# motherboard.net
KiCad netlist of a schematic drawn in EAGLE
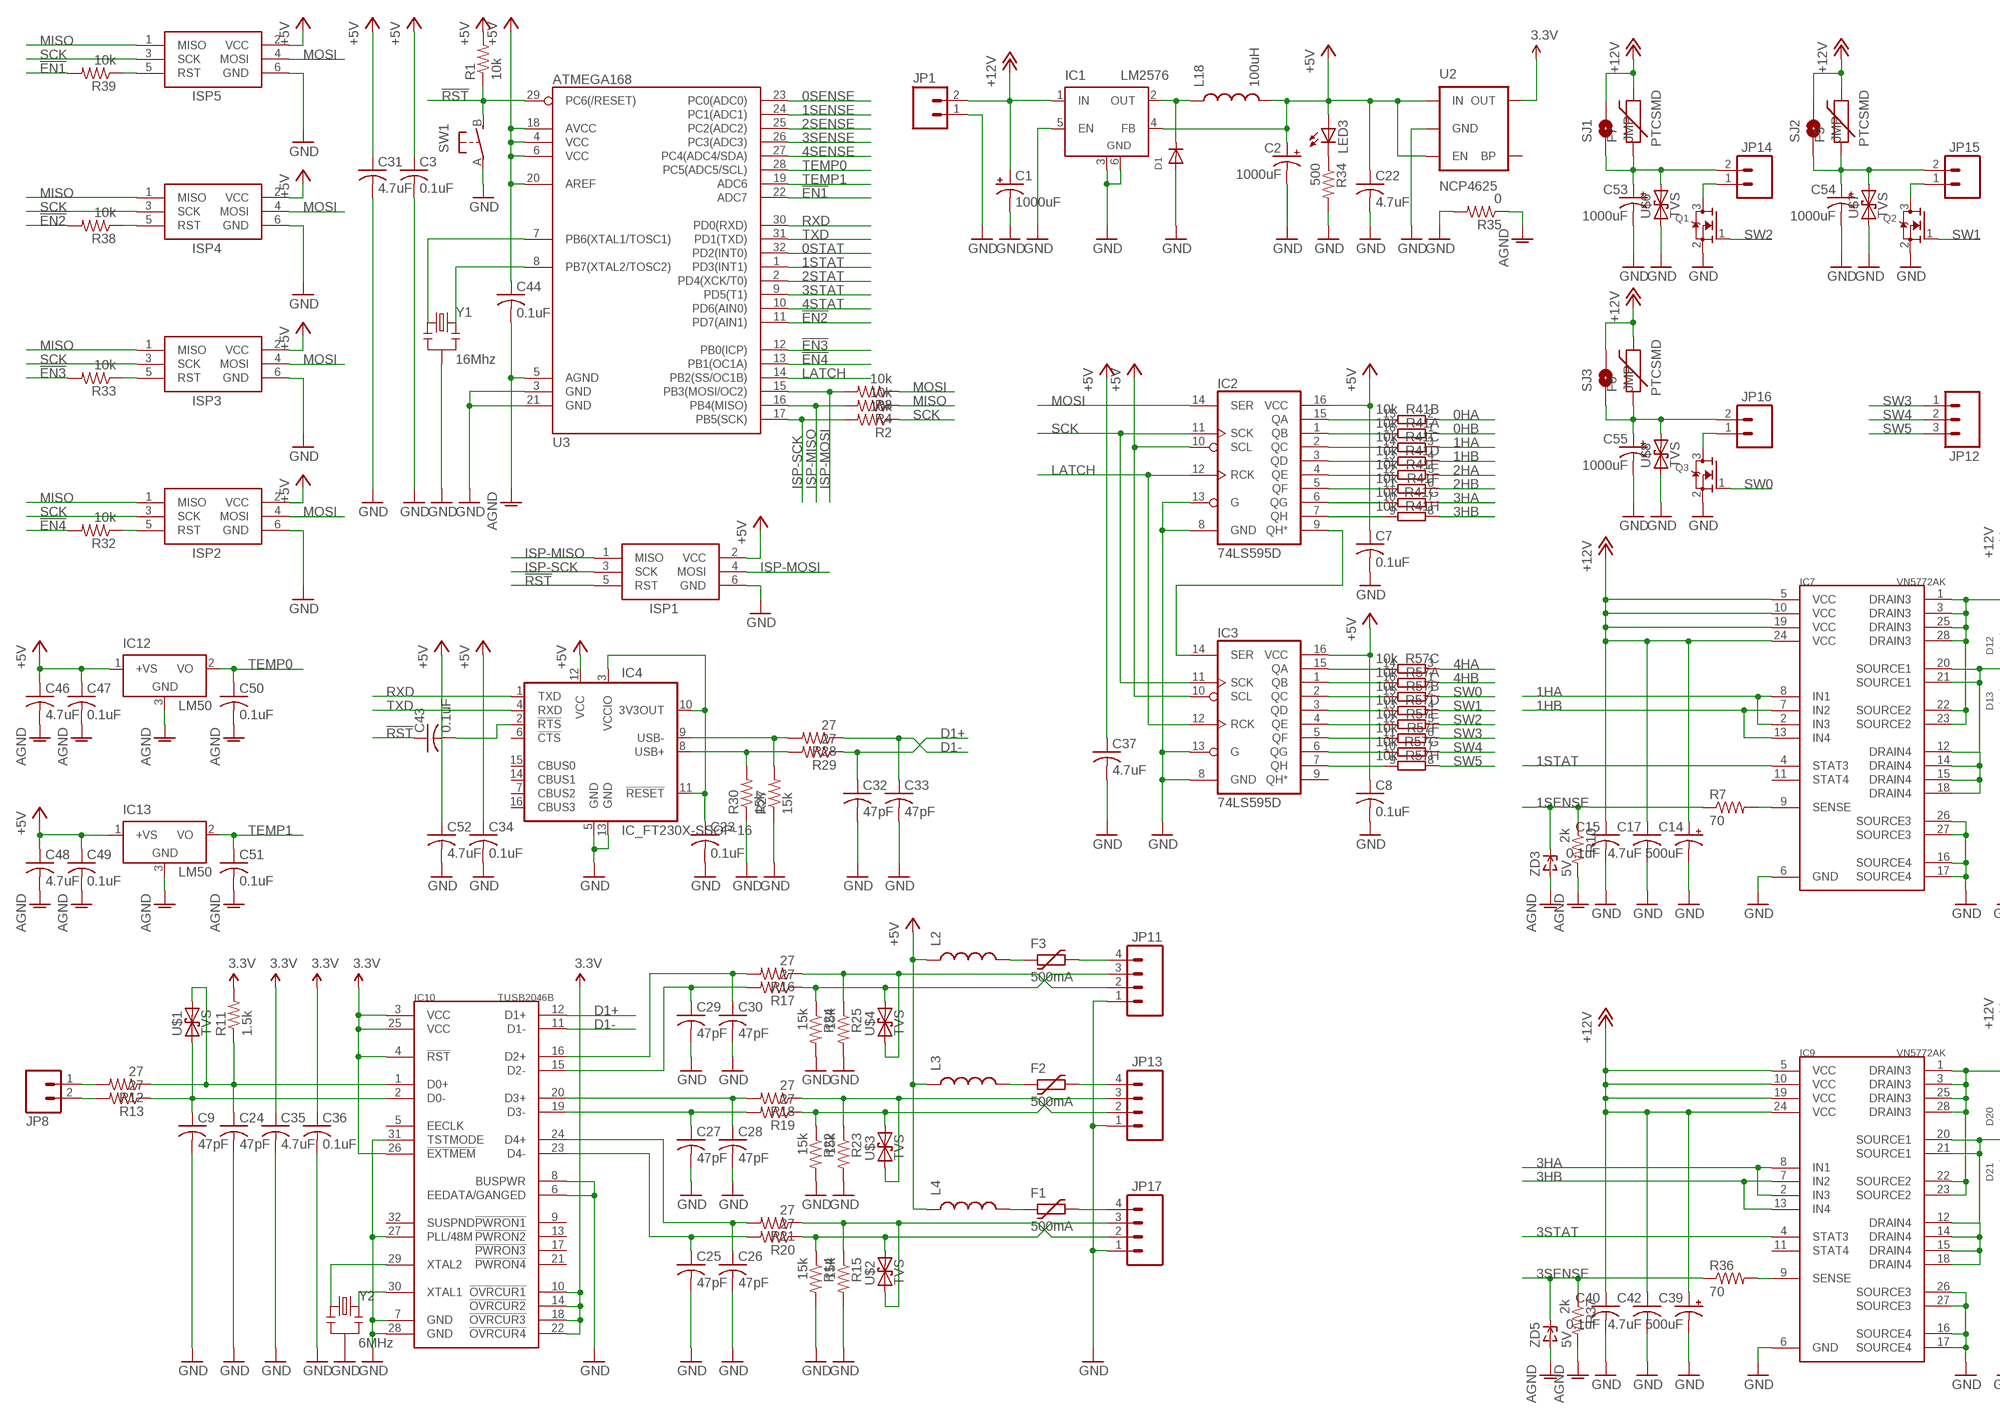
[diagram p0: schematic, sheet 1, part 1 of 2]
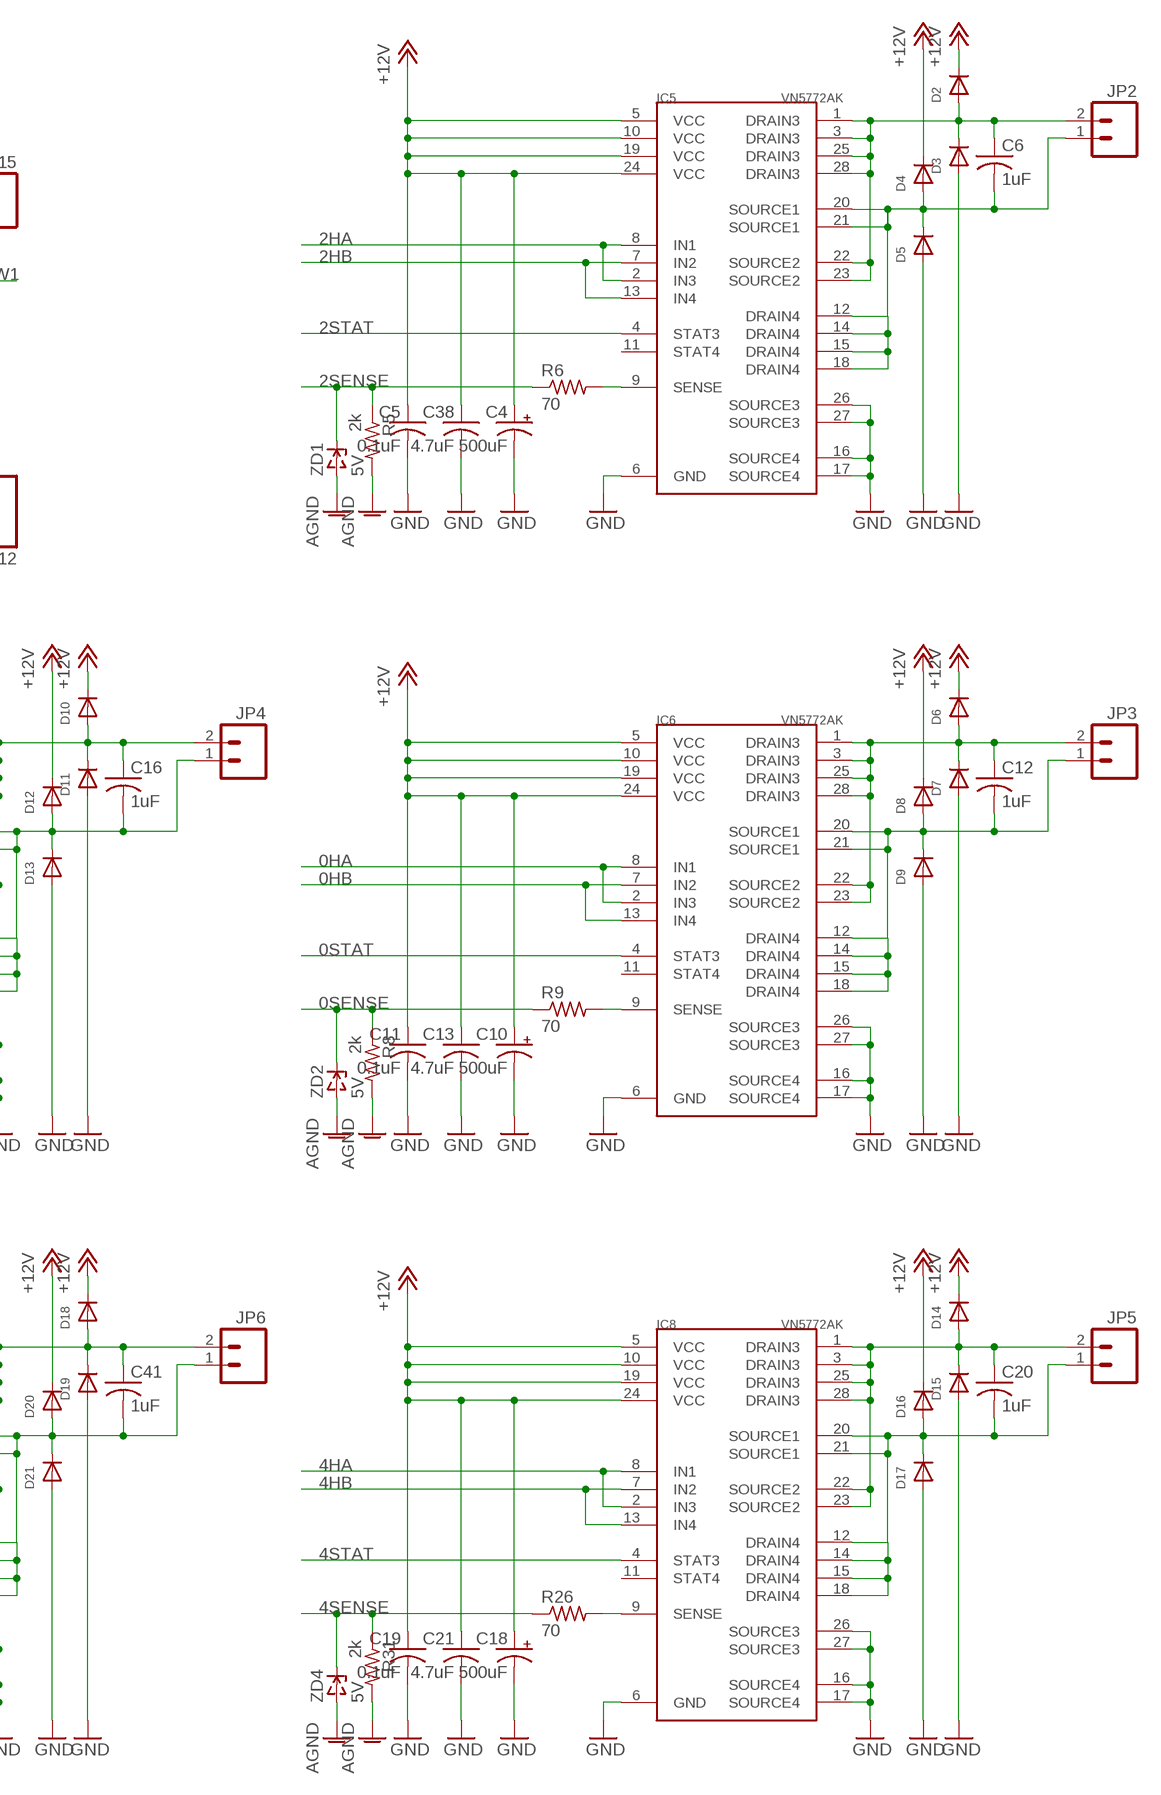
[diagram p1: schematic, sheet 1, part 2 of 2]

(export (version "E")
  (design (tool "Eeschema 10.0.6"))
  (components
    (comp (ref "C1")
      (value "1000uF")
      (footprint "eagle-import:153CLV-0807")
      (libsource (lib "eagle-import") (part "CPOL-US153CLV-0807"))
    )
    (comp (ref "C2")
      (value "1000uF")
      (footprint "eagle-import:153CLV-0807")
      (libsource (lib "eagle-import") (part "CPOL-US153CLV-0807"))
    )
    (comp (ref "C3")
      (value "0.1uF")
      (footprint "eagle-import:C1206")
      (libsource (lib "eagle-import") (part "C-USC1206"))
    )
    (comp (ref "C4")
      (value "500uF")
      (footprint "eagle-import:153CLV-0807")
      (libsource (lib "eagle-import") (part "CPOL-US153CLV-0807"))
    )
    (comp (ref "C5")
      (value "0.1uF")
      (footprint "eagle-import:C1206")
      (libsource (lib "eagle-import") (part "C-USC1206"))
    )
    (comp (ref "C6")
      (value "1uF")
      (footprint "eagle-import:C1206")
      (libsource (lib "eagle-import") (part "C-USC1206"))
    )
    (comp (ref "C7")
      (value "0.1uF")
      (footprint "eagle-import:C1206")
      (libsource (lib "eagle-import") (part "C-USC1206"))
    )
    (comp (ref "C8")
      (value "0.1uF")
      (footprint "eagle-import:C1206")
      (libsource (lib "eagle-import") (part "C-USC1206"))
    )
    (comp (ref "C9")
      (value "47pF")
      (footprint "eagle-import:C1206")
      (libsource (lib "eagle-import") (part "C-USC1206"))
    )
    (comp (ref "C10")
      (value "500uF")
      (footprint "eagle-import:153CLV-0807")
      (libsource (lib "eagle-import") (part "CPOL-US153CLV-0807"))
    )
    (comp (ref "C11")
      (value "0.1uF")
      (footprint "eagle-import:C1206")
      (libsource (lib "eagle-import") (part "C-USC1206"))
    )
    (comp (ref "C12")
      (value "1uF")
      (footprint "eagle-import:C1206")
      (libsource (lib "eagle-import") (part "C-USC1206"))
    )
    (comp (ref "C13")
      (value "4.7uF")
      (footprint "eagle-import:C1206")
      (libsource (lib "eagle-import") (part "C-USC1206"))
    )
    (comp (ref "C14")
      (value "500uF")
      (footprint "eagle-import:153CLV-0807")
      (libsource (lib "eagle-import") (part "CPOL-US153CLV-0807"))
    )
    (comp (ref "C15")
      (value "0.1uF")
      (footprint "eagle-import:C1206")
      (libsource (lib "eagle-import") (part "C-USC1206"))
    )
    (comp (ref "C16")
      (value "1uF")
      (footprint "eagle-import:C1206")
      (libsource (lib "eagle-import") (part "C-USC1206"))
    )
    (comp (ref "C17")
      (value "4.7uF")
      (footprint "eagle-import:C1206")
      (libsource (lib "eagle-import") (part "C-USC1206"))
    )
    (comp (ref "C18")
      (value "500uF")
      (footprint "eagle-import:153CLV-0807")
      (libsource (lib "eagle-import") (part "CPOL-US153CLV-0807"))
    )
    (comp (ref "C19")
      (value "0.1uF")
      (footprint "eagle-import:C1206")
      (libsource (lib "eagle-import") (part "C-USC1206"))
    )
    (comp (ref "C20")
      (value "1uF")
      (footprint "eagle-import:C1206")
      (libsource (lib "eagle-import") (part "C-USC1206"))
    )
    (comp (ref "C21")
      (value "4.7uF")
      (footprint "eagle-import:C1206")
      (libsource (lib "eagle-import") (part "C-USC1206"))
    )
    (comp (ref "C22")
      (value "4.7uF")
      (footprint "eagle-import:C1206")
      (libsource (lib "eagle-import") (part "C-USC1206"))
    )
    (comp (ref "C23")
      (value "0.1uF")
      (footprint "eagle-import:C1206")
      (libsource (lib "eagle-import") (part "C-USC1206"))
    )
    (comp (ref "C24")
      (value "47pF")
      (footprint "eagle-import:C1206")
      (libsource (lib "eagle-import") (part "C-USC1206"))
    )
    (comp (ref "C25")
      (value "47pF")
      (footprint "eagle-import:C1206")
      (libsource (lib "eagle-import") (part "C-USC1206"))
    )
    (comp (ref "C26")
      (value "47pF")
      (footprint "eagle-import:C1206")
      (libsource (lib "eagle-import") (part "C-USC1206"))
    )
    (comp (ref "C27")
      (value "47pF")
      (footprint "eagle-import:C1206")
      (libsource (lib "eagle-import") (part "C-USC1206"))
    )
    (comp (ref "C28")
      (value "47pF")
      (footprint "eagle-import:C1206")
      (libsource (lib "eagle-import") (part "C-USC1206"))
    )
    (comp (ref "C29")
      (value "47pF")
      (footprint "eagle-import:C1206")
      (libsource (lib "eagle-import") (part "C-USC1206"))
    )
    (comp (ref "C30")
      (value "47pF")
      (footprint "eagle-import:C1206")
      (libsource (lib "eagle-import") (part "C-USC1206"))
    )
    (comp (ref "C31")
      (value "4.7uF")
      (footprint "eagle-import:C1206")
      (libsource (lib "eagle-import") (part "C-USC1206"))
    )
    (comp (ref "C32")
      (value "47pF")
      (footprint "eagle-import:C1206")
      (libsource (lib "eagle-import") (part "C-USC1206"))
    )
    (comp (ref "C33")
      (value "47pF")
      (footprint "eagle-import:C1206")
      (libsource (lib "eagle-import") (part "C-USC1206"))
    )
    (comp (ref "C34")
      (value "0.1uF")
      (footprint "eagle-import:C1206")
      (libsource (lib "eagle-import") (part "C-USC1206"))
    )
    (comp (ref "C35")
      (value "4.7uF")
      (footprint "eagle-import:C1206")
      (libsource (lib "eagle-import") (part "C-USC1206"))
    )
    (comp (ref "C36")
      (value "0.1uF")
      (footprint "eagle-import:C1206")
      (libsource (lib "eagle-import") (part "C-USC1206"))
    )
    (comp (ref "C37")
      (value "4.7uF")
      (footprint "eagle-import:C1206")
      (libsource (lib "eagle-import") (part "C-USC1206"))
    )
    (comp (ref "C38")
      (value "4.7uF")
      (footprint "eagle-import:C1206")
      (libsource (lib "eagle-import") (part "C-USC1206"))
    )
    (comp (ref "C39")
      (value "500uF")
      (footprint "eagle-import:153CLV-0807")
      (libsource (lib "eagle-import") (part "CPOL-US153CLV-0807"))
    )
    (comp (ref "C40")
      (value "0.1uF")
      (footprint "eagle-import:C1206")
      (libsource (lib "eagle-import") (part "C-USC1206"))
    )
    (comp (ref "C41")
      (value "1uF")
      (footprint "eagle-import:C1206")
      (libsource (lib "eagle-import") (part "C-USC1206"))
    )
    (comp (ref "C42")
      (value "4.7uF")
      (footprint "eagle-import:C1206")
      (libsource (lib "eagle-import") (part "C-USC1206"))
    )
    (comp (ref "C43")
      (value "0.1uF")
      (footprint "eagle-import:C1206")
      (libsource (lib "eagle-import") (part "C-USC1206"))
    )
    (comp (ref "C44")
      (value "0.1uF")
      (footprint "eagle-import:C1206")
      (libsource (lib "eagle-import") (part "C-USC1206"))
    )
    (comp (ref "C46")
      (value "4.7uF")
      (footprint "eagle-import:C1206")
      (libsource (lib "eagle-import") (part "C-USC1206"))
    )
    (comp (ref "C47")
      (value "0.1uF")
      (footprint "eagle-import:C1206")
      (libsource (lib "eagle-import") (part "C-USC1206"))
    )
    (comp (ref "C48")
      (value "4.7uF")
      (footprint "eagle-import:C1206")
      (libsource (lib "eagle-import") (part "C-USC1206"))
    )
    (comp (ref "C49")
      (value "0.1uF")
      (footprint "eagle-import:C1206")
      (libsource (lib "eagle-import") (part "C-USC1206"))
    )
    (comp (ref "C50")
      (value "0.1uF")
      (footprint "eagle-import:C1206")
      (libsource (lib "eagle-import") (part "C-USC1206"))
    )
    (comp (ref "C51")
      (value "0.1uF")
      (footprint "eagle-import:C1206")
      (libsource (lib "eagle-import") (part "C-USC1206"))
    )
    (comp (ref "C52")
      (value "4.7uF")
      (footprint "eagle-import:C1206")
      (libsource (lib "eagle-import") (part "C-USC1206"))
    )
    (comp (ref "C53")
      (value "1000uF")
      (footprint "eagle-import:153CLV-0807")
      (libsource (lib "eagle-import") (part "CPOL-US153CLV-0807"))
    )
    (comp (ref "C54")
      (value "1000uF")
      (footprint "eagle-import:153CLV-0807")
      (libsource (lib "eagle-import") (part "CPOL-US153CLV-0807"))
    )
    (comp (ref "C55")
      (value "1000uF")
      (footprint "eagle-import:153CLV-0807")
      (libsource (lib "eagle-import") (part "CPOL-US153CLV-0807"))
    )
    (comp (ref "D1")
      (value "DIODESMA")
      (footprint "eagle-import:SMADIODE")
      (libsource (lib "eagle-import") (part "DIODESMA"))
    )
    (comp (ref "D2")
      (value "DIODESOD-123")
      (footprint "eagle-import:SOD-123")
      (libsource (lib "eagle-import") (part "DIODESOD-123"))
    )
    (comp (ref "D3")
      (value "DIODESOD-123")
      (footprint "eagle-import:SOD-123")
      (libsource (lib "eagle-import") (part "DIODESOD-123"))
    )
    (comp (ref "D4")
      (value "DIODESOD-123")
      (footprint "eagle-import:SOD-123")
      (libsource (lib "eagle-import") (part "DIODESOD-123"))
    )
    (comp (ref "D5")
      (value "DIODESOD-123")
      (footprint "eagle-import:SOD-123")
      (libsource (lib "eagle-import") (part "DIODESOD-123"))
    )
    (comp (ref "D6")
      (value "DIODESOD-123")
      (footprint "eagle-import:SOD-123")
      (libsource (lib "eagle-import") (part "DIODESOD-123"))
    )
    (comp (ref "D7")
      (value "DIODESOD-123")
      (footprint "eagle-import:SOD-123")
      (libsource (lib "eagle-import") (part "DIODESOD-123"))
    )
    (comp (ref "D8")
      (value "DIODESOD-123")
      (footprint "eagle-import:SOD-123")
      (libsource (lib "eagle-import") (part "DIODESOD-123"))
    )
    (comp (ref "D9")
      (value "DIODESOD-123")
      (footprint "eagle-import:SOD-123")
      (libsource (lib "eagle-import") (part "DIODESOD-123"))
    )
    (comp (ref "D10")
      (value "DIODESOD-123")
      (footprint "eagle-import:SOD-123")
      (libsource (lib "eagle-import") (part "DIODESOD-123"))
    )
    (comp (ref "D11")
      (value "DIODESOD-123")
      (footprint "eagle-import:SOD-123")
      (libsource (lib "eagle-import") (part "DIODESOD-123"))
    )
    (comp (ref "D12")
      (value "DIODESOD-123")
      (footprint "eagle-import:SOD-123")
      (libsource (lib "eagle-import") (part "DIODESOD-123"))
    )
    (comp (ref "D13")
      (value "DIODESOD-123")
      (footprint "eagle-import:SOD-123")
      (libsource (lib "eagle-import") (part "DIODESOD-123"))
    )
    (comp (ref "D14")
      (value "DIODESOD-123")
      (footprint "eagle-import:SOD-123")
      (libsource (lib "eagle-import") (part "DIODESOD-123"))
    )
    (comp (ref "D15")
      (value "DIODESOD-123")
      (footprint "eagle-import:SOD-123")
      (libsource (lib "eagle-import") (part "DIODESOD-123"))
    )
    (comp (ref "D16")
      (value "DIODESOD-123")
      (footprint "eagle-import:SOD-123")
      (libsource (lib "eagle-import") (part "DIODESOD-123"))
    )
    (comp (ref "D17")
      (value "DIODESOD-123")
      (footprint "eagle-import:SOD-123")
      (libsource (lib "eagle-import") (part "DIODESOD-123"))
    )
    (comp (ref "D18")
      (value "DIODESOD-123")
      (footprint "eagle-import:SOD-123")
      (libsource (lib "eagle-import") (part "DIODESOD-123"))
    )
    (comp (ref "D19")
      (value "DIODESOD-123")
      (footprint "eagle-import:SOD-123")
      (libsource (lib "eagle-import") (part "DIODESOD-123"))
    )
    (comp (ref "D20")
      (value "DIODESOD-123")
      (footprint "eagle-import:SOD-123")
      (libsource (lib "eagle-import") (part "DIODESOD-123"))
    )
    (comp (ref "D21")
      (value "DIODESOD-123")
      (footprint "eagle-import:SOD-123")
      (libsource (lib "eagle-import") (part "DIODESOD-123"))
    )
    (comp (ref "F1")
      (value "500mA")
      (footprint "eagle-import:PTC1812L")
      (libsource (lib "eagle-import") (part "FUSE_PTC-1812"))
    )
    (comp (ref "F2")
      (value "500mA")
      (footprint "eagle-import:PTC1812L")
      (libsource (lib "eagle-import") (part "FUSE_PTC-1812"))
    )
    (comp (ref "F3")
      (value "500mA")
      (footprint "eagle-import:PTC1812L")
      (libsource (lib "eagle-import") (part "FUSE_PTC-1812"))
    )
    (comp (ref "F5")
      (value "PTCSMD")
      (footprint "eagle-import:PTC-1206")
      (libsource (lib "eagle-import") (part "PTCSMD"))
    )
    (comp (ref "F6")
      (value "PTCSMD")
      (footprint "eagle-import:PTC-1206")
      (libsource (lib "eagle-import") (part "PTCSMD"))
    )
    (comp (ref "F7")
      (value "PTCSMD")
      (footprint "eagle-import:PTC-1206")
      (libsource (lib "eagle-import") (part "PTCSMD"))
    )
    (comp (ref "IC1")
      (value "LM2576")
      (footprint "eagle-import:TO263-5")
      (libsource (lib "eagle-import") (part "LM2596S"))
    )
    (comp (ref "IC2")
      (value "74LS595D")
      (footprint "eagle-import:SO16")
      (libsource (lib "eagle-import") (part "74595DLS"))
    )
    (comp (ref "IC3")
      (value "74LS595D")
      (footprint "eagle-import:SO16")
      (libsource (lib "eagle-import") (part "74595DLS"))
    )
    (comp (ref "IC4")
      (value "IC_FT230X-SSOP-16")
      (footprint "eagle-import:SSOP-16-FTDI")
      (libsource (lib "eagle-import") (part "IC_FT230X-SSOP-16"))
    )
    (comp (ref "IC5")
      (value "VN5772AK")
      (footprint "eagle-import:SO-28")
      (libsource (lib "eagle-import") (part "VN5772AK"))
    )
    (comp (ref "IC6")
      (value "VN5772AK")
      (footprint "eagle-import:SO-28")
      (libsource (lib "eagle-import") (part "VN5772AK"))
    )
    (comp (ref "IC7")
      (value "VN5772AK")
      (footprint "eagle-import:SO-28")
      (libsource (lib "eagle-import") (part "VN5772AK"))
    )
    (comp (ref "IC8")
      (value "VN5772AK")
      (footprint "eagle-import:SO-28")
      (libsource (lib "eagle-import") (part "VN5772AK"))
    )
    (comp (ref "IC9")
      (value "VN5772AK")
      (footprint "eagle-import:SO-28")
      (libsource (lib "eagle-import") (part "VN5772AK"))
    )
    (comp (ref "IC10")
      (value "TUSB2046B")
      (footprint "eagle-import:LQFP-32")
      (libsource (lib "eagle-import") (part "TUSB2046B"))
    )
    (comp (ref "IC12")
      (value "LM50")
      (footprint "eagle-import:SOT23")
      (libsource (lib "eagle-import") (part "LM50"))
    )
    (comp (ref "IC13")
      (value "LM50")
      (footprint "eagle-import:SOT23")
      (libsource (lib "eagle-import") (part "LM50"))
    )
    (comp (ref "ISP1")
      (value "AVRISP-6")
      (footprint "eagle-import:AVRISP")
      (libsource (lib "eagle-import") (part "AVRISP-6"))
    )
    (comp (ref "ISP2")
      (value "AVRISP-6")
      (footprint "eagle-import:AVRISP")
      (libsource (lib "eagle-import") (part "AVRISP-6"))
    )
    (comp (ref "ISP3")
      (value "AVRISP-6")
      (footprint "eagle-import:AVRISP")
      (libsource (lib "eagle-import") (part "AVRISP-6"))
    )
    (comp (ref "ISP4")
      (value "AVRISP-6")
      (footprint "eagle-import:AVRISP")
      (libsource (lib "eagle-import") (part "AVRISP-6"))
    )
    (comp (ref "ISP5")
      (value "AVRISP-6")
      (footprint "eagle-import:AVRISP")
      (libsource (lib "eagle-import") (part "AVRISP-6"))
    )
    (comp (ref "JP1")
      (value "M023.5MM")
      (footprint "eagle-import:SCREWTERMINAL-3.5MM-2")
      (libsource (lib "eagle-import") (part "M023.5MM"))
    )
    (comp (ref "JP2")
      (value "M023.5MM")
      (footprint "eagle-import:SCREWTERMINAL-3.5MM-2")
      (libsource (lib "eagle-import") (part "M023.5MM"))
    )
    (comp (ref "JP3")
      (value "M023.5MM")
      (footprint "eagle-import:SCREWTERMINAL-3.5MM-2")
      (libsource (lib "eagle-import") (part "M023.5MM"))
    )
    (comp (ref "JP4")
      (value "M023.5MM")
      (footprint "eagle-import:SCREWTERMINAL-3.5MM-2")
      (libsource (lib "eagle-import") (part "M023.5MM"))
    )
    (comp (ref "JP5")
      (value "M023.5MM")
      (footprint "eagle-import:SCREWTERMINAL-3.5MM-2")
      (libsource (lib "eagle-import") (part "M023.5MM"))
    )
    (comp (ref "JP6")
      (value "M023.5MM")
      (footprint "eagle-import:SCREWTERMINAL-3.5MM-2")
      (libsource (lib "eagle-import") (part "M023.5MM"))
    )
    (comp (ref "JP8")
      (value "M023.5MM")
      (footprint "eagle-import:SCREWTERMINAL-3.5MM-2")
      (libsource (lib "eagle-import") (part "M023.5MM"))
    )
    (comp (ref "JP11")
      (value "M04SCREW")
      (footprint "eagle-import:SCREWTERMINAL-3.5MM-4")
      (libsource (lib "eagle-import") (part "M04SCREW"))
    )
    (comp (ref "JP12")
      (value "M03PTH")
      (footprint "eagle-import:1X03")
      (libsource (lib "eagle-import") (part "M03PTH"))
    )
    (comp (ref "JP13")
      (value "M04SCREW")
      (footprint "eagle-import:SCREWTERMINAL-3.5MM-4")
      (libsource (lib "eagle-import") (part "M04SCREW"))
    )
    (comp (ref "JP14")
      (value "M023.5MM")
      (footprint "eagle-import:SCREWTERMINAL-3.5MM-2")
      (libsource (lib "eagle-import") (part "M023.5MM"))
    )
    (comp (ref "JP15")
      (value "M023.5MM")
      (footprint "eagle-import:SCREWTERMINAL-3.5MM-2")
      (libsource (lib "eagle-import") (part "M023.5MM"))
    )
    (comp (ref "JP16")
      (value "M023.5MM")
      (footprint "eagle-import:SCREWTERMINAL-3.5MM-2")
      (libsource (lib "eagle-import") (part "M023.5MM"))
    )
    (comp (ref "JP17")
      (value "M04SCREW")
      (footprint "eagle-import:SCREWTERMINAL-3.5MM-4")
      (libsource (lib "eagle-import") (part "M04SCREW"))
    )
    (comp (ref "L2")
      (value "INDUCTOR1206H*")
      (footprint "eagle-import:INDUCTOR-1206")
      (libsource (lib "eagle-import") (part "INDUCTORH1206"))
    )
    (comp (ref "L3")
      (value "INDUCTOR1206H*")
      (footprint "eagle-import:INDUCTOR-1206")
      (libsource (lib "eagle-import") (part "INDUCTORH1206"))
    )
    (comp (ref "L4")
      (value "INDUCTOR1206H*")
      (footprint "eagle-import:INDUCTOR-1206")
      (libsource (lib "eagle-import") (part "INDUCTORH1206"))
    )
    (comp (ref "L18")
      (value "100uH")
      (footprint "eagle-import:CDRH125")
      (libsource (lib "eagle-import") (part "INDUCTORPWR"))
    )
    (comp (ref "LED3")
      (value "LEDCHIPLED_1206")
      (footprint "eagle-import:CHIPLED_1206")
      (libsource (lib "eagle-import") (part "LEDCHIPLED_1206"))
    )
    (comp (ref "Q1")
      (value "MOSFET-NREFLOW")
      (footprint "eagle-import:SOT23")
      (libsource (lib "eagle-import") (part "MOSFET-NREFLOW"))
    )
    (comp (ref "Q2")
      (value "MOSFET-NREFLOW")
      (footprint "eagle-import:SOT23")
      (libsource (lib "eagle-import") (part "MOSFET-NREFLOW"))
    )
    (comp (ref "Q3")
      (value "MOSFET-NREFLOW")
      (footprint "eagle-import:SOT23")
      (libsource (lib "eagle-import") (part "MOSFET-NREFLOW"))
    )
    (comp (ref "R1")
      (value "10k")
      (footprint "eagle-import:R1206")
      (libsource (lib "eagle-import") (part "R-US_R1206"))
    )
    (comp (ref "R2")
      (value "10k")
      (footprint "eagle-import:R1206")
      (libsource (lib "eagle-import") (part "R-US_R1206"))
    )
    (comp (ref "R3")
      (value "10k")
      (footprint "eagle-import:R1206")
      (libsource (lib "eagle-import") (part "R-US_R1206"))
    )
    (comp (ref "R4")
      (value "10k")
      (footprint "eagle-import:R1206")
      (libsource (lib "eagle-import") (part "R-US_R1206"))
    )
    (comp (ref "R5")
      (value "2k")
      (footprint "eagle-import:R1206")
      (libsource (lib "eagle-import") (part "R-US_R1206"))
    )
    (comp (ref "R6")
      (value "70")
      (footprint "eagle-import:R1206")
      (libsource (lib "eagle-import") (part "R-US_R1206"))
    )
    (comp (ref "R7")
      (value "70")
      (footprint "eagle-import:R1206")
      (libsource (lib "eagle-import") (part "R-US_R1206"))
    )
    (comp (ref "R8")
      (value "2k")
      (footprint "eagle-import:R1206")
      (libsource (lib "eagle-import") (part "R-US_R1206"))
    )
    (comp (ref "R9")
      (value "70")
      (footprint "eagle-import:R1206")
      (libsource (lib "eagle-import") (part "R-US_R1206"))
    )
    (comp (ref "R10")
      (value "2k")
      (footprint "eagle-import:R1206")
      (libsource (lib "eagle-import") (part "R-US_R1206"))
    )
    (comp (ref "R11")
      (value "1.5k")
      (footprint "eagle-import:R1206")
      (libsource (lib "eagle-import") (part "R-US_R1206"))
    )
    (comp (ref "R12")
      (value "27")
      (footprint "eagle-import:R1206")
      (libsource (lib "eagle-import") (part "R-US_R1206"))
    )
    (comp (ref "R13")
      (value "27")
      (footprint "eagle-import:R1206")
      (libsource (lib "eagle-import") (part "R-US_R1206"))
    )
    (comp (ref "R14")
      (value "15k")
      (footprint "eagle-import:R1206")
      (libsource (lib "eagle-import") (part "R-US_R1206"))
    )
    (comp (ref "R15")
      (value "15k")
      (footprint "eagle-import:R1206")
      (libsource (lib "eagle-import") (part "R-US_R1206"))
    )
    (comp (ref "R16")
      (value "27")
      (footprint "eagle-import:R1206")
      (libsource (lib "eagle-import") (part "R-US_R1206"))
    )
    (comp (ref "R17")
      (value "27")
      (footprint "eagle-import:R1206")
      (libsource (lib "eagle-import") (part "R-US_R1206"))
    )
    (comp (ref "R18")
      (value "27")
      (footprint "eagle-import:R1206")
      (libsource (lib "eagle-import") (part "R-US_R1206"))
    )
    (comp (ref "R19")
      (value "27")
      (footprint "eagle-import:R1206")
      (libsource (lib "eagle-import") (part "R-US_R1206"))
    )
    (comp (ref "R20")
      (value "27")
      (footprint "eagle-import:R1206")
      (libsource (lib "eagle-import") (part "R-US_R1206"))
    )
    (comp (ref "R21")
      (value "27")
      (footprint "eagle-import:R1206")
      (libsource (lib "eagle-import") (part "R-US_R1206"))
    )
    (comp (ref "R22")
      (value "15k")
      (footprint "eagle-import:R1206")
      (libsource (lib "eagle-import") (part "R-US_R1206"))
    )
    (comp (ref "R23")
      (value "15k")
      (footprint "eagle-import:R1206")
      (libsource (lib "eagle-import") (part "R-US_R1206"))
    )
    (comp (ref "R24")
      (value "15k")
      (footprint "eagle-import:R1206")
      (libsource (lib "eagle-import") (part "R-US_R1206"))
    )
    (comp (ref "R25")
      (value "15k")
      (footprint "eagle-import:R1206")
      (libsource (lib "eagle-import") (part "R-US_R1206"))
    )
    (comp (ref "R26")
      (value "70")
      (footprint "eagle-import:R1206")
      (libsource (lib "eagle-import") (part "R-US_R1206"))
    )
    (comp (ref "R27")
      (value "15k")
      (footprint "eagle-import:R1206")
      (libsource (lib "eagle-import") (part "R-US_R1206"))
    )
    (comp (ref "R28")
      (value "27")
      (footprint "eagle-import:R1206")
      (libsource (lib "eagle-import") (part "R-US_R1206"))
    )
    (comp (ref "R29")
      (value "27")
      (footprint "eagle-import:R1206")
      (libsource (lib "eagle-import") (part "R-US_R1206"))
    )
    (comp (ref "R30")
      (value "15k")
      (footprint "eagle-import:R1206")
      (libsource (lib "eagle-import") (part "R-US_R1206"))
    )
    (comp (ref "R31")
      (value "2k")
      (footprint "eagle-import:R1206")
      (libsource (lib "eagle-import") (part "R-US_R1206"))
    )
    (comp (ref "R32")
      (value "10k")
      (footprint "eagle-import:R1206")
      (libsource (lib "eagle-import") (part "R-US_R1206"))
    )
    (comp (ref "R33")
      (value "10k")
      (footprint "eagle-import:R1206")
      (libsource (lib "eagle-import") (part "R-US_R1206"))
    )
    (comp (ref "R34")
      (value "500")
      (footprint "eagle-import:R1206")
      (libsource (lib "eagle-import") (part "R-US_R1206"))
    )
    (comp (ref "R35")
      (value "0")
      (footprint "eagle-import:R1206")
      (libsource (lib "eagle-import") (part "R-US_R1206"))
    )
    (comp (ref "R36")
      (value "70")
      (footprint "eagle-import:R1206")
      (libsource (lib "eagle-import") (part "R-US_R1206"))
    )
    (comp (ref "R37")
      (value "2k")
      (footprint "eagle-import:R1206")
      (libsource (lib "eagle-import") (part "R-US_R1206"))
    )
    (comp (ref "R38")
      (value "10k")
      (footprint "eagle-import:R1206")
      (libsource (lib "eagle-import") (part "R-US_R1206"))
    )
    (comp (ref "R39")
      (value "10k")
      (footprint "eagle-import:R1206")
      (libsource (lib "eagle-import") (part "R-US_R1206"))
    )
    (comp (ref "R41")
      (value "10k")
      (footprint "eagle-import:SO16")
      (libsource (lib "eagle-import") (part "2NBS16-8E"))
    )
    (comp (ref "R57")
      (value "10k")
      (footprint "eagle-import:SO16")
      (libsource (lib "eagle-import") (part "2NBS16-8E"))
    )
    (comp (ref "SJ1")
      (value "JMP")
      (footprint "eagle-import:SJ_2S-NO")
      (libsource (lib "eagle-import") (part "SOLDERJUMPER-OLDNO"))
    )
    (comp (ref "SJ2")
      (value "JMP")
      (footprint "eagle-import:SJ_2S-NO")
      (libsource (lib "eagle-import") (part "SOLDERJUMPER-OLDNO"))
    )
    (comp (ref "SJ3")
      (value "JMP")
      (footprint "eagle-import:SJ_2S-NO")
      (libsource (lib "eagle-import") (part "SOLDERJUMPER-OLDNO"))
    )
    (comp (ref "SW1")
      (value "FSMSM")
      (footprint "eagle-import:FSMSM")
      (libsource (lib "eagle-import") (part "FSMSM"))
    )
    (comp (ref "U$1")
      (value "TVS")
      (footprint "eagle-import:SMA-DIODE")
      (libsource (lib "eagle-import") (part "TVS"))
    )
    (comp (ref "U$2")
      (value "TVS")
      (footprint "eagle-import:SMA-DIODE")
      (libsource (lib "eagle-import") (part "TVS"))
    )
    (comp (ref "U$3")
      (value "TVS")
      (footprint "eagle-import:SMA-DIODE")
      (libsource (lib "eagle-import") (part "TVS"))
    )
    (comp (ref "U$4")
      (value "TVS")
      (footprint "eagle-import:SMA-DIODE")
      (libsource (lib "eagle-import") (part "TVS"))
    )
    (comp (ref "U$6")
      (value "TVS")
      (footprint "eagle-import:SMA-DIODE")
      (libsource (lib "eagle-import") (part "TVS"))
    )
    (comp (ref "U$7")
      (value "TVS")
      (footprint "eagle-import:SMA-DIODE")
      (libsource (lib "eagle-import") (part "TVS"))
    )
    (comp (ref "U$8")
      (value "TVS")
      (footprint "eagle-import:SMA-DIODE")
      (libsource (lib "eagle-import") (part "TVS"))
    )
    (comp (ref "U2")
      (value "NCP4625")
      (footprint "eagle-import:SOT23-5")
      (libsource (lib "eagle-import") (part "V_REG_LDOSMD"))
    )
    (comp (ref "U3")
      (value "ATMEGA168")
      (footprint "eagle-import:TQFP32-08")
      (libsource (lib "eagle-import") (part "ATMEGA168"))
    )
    (comp (ref "Y1")
      (value "16Mhz")
      (footprint "eagle-import:RESONATOR-SMD")
      (libsource (lib "eagle-import") (part "RESONATORSMD"))
    )
    (comp (ref "Y2")
      (value "6MHz")
      (footprint "eagle-import:RESONATOR-SMD")
      (libsource (lib "eagle-import") (part "RESONATORSMD"))
    )
    (comp (ref "ZD1")
      (value "5V")
      (footprint "eagle-import:SOD-123")
      (libsource (lib "eagle-import") (part "ZENERSOD-123"))
    )
    (comp (ref "ZD2")
      (value "5V")
      (footprint "eagle-import:SOD-123")
      (libsource (lib "eagle-import") (part "ZENERSOD-123"))
    )
    (comp (ref "ZD3")
      (value "5V")
      (footprint "eagle-import:SOD-123")
      (libsource (lib "eagle-import") (part "ZENERSOD-123"))
    )
    (comp (ref "ZD4")
      (value "5V")
      (footprint "eagle-import:SOD-123")
      (libsource (lib "eagle-import") (part "ZENERSOD-123"))
    )
    (comp (ref "ZD5")
      (value "5V")
      (footprint "eagle-import:SOD-123")
      (libsource (lib "eagle-import") (part "ZENERSOD-123"))
    )
  )
  (nets
    (net (code "1") (name "+5V") (class "Default")
      (node (ref "C2") (pin "+") (pinfunction "+_+") (pintype "passive"))
      (node (ref "C22") (pin "1") (pinfunction "1_1") (pintype "passive"))
      (node (ref "C3") (pin "1") (pinfunction "1_1") (pintype "passive"))
      (node (ref "C31") (pin "1") (pinfunction "1_1") (pintype "passive"))
      (node (ref "C34") (pin "1") (pinfunction "1_1") (pintype "passive"))
      (node (ref "C37") (pin "1") (pinfunction "1_1") (pintype "passive"))
      (node (ref "C44") (pin "1") (pinfunction "1_1") (pintype "passive"))
      (node (ref "C46") (pin "1") (pinfunction "1_1") (pintype "passive"))
      (node (ref "C47") (pin "1") (pinfunction "1_1") (pintype "passive"))
      (node (ref "C48") (pin "1") (pinfunction "1_1") (pintype "passive"))
      (node (ref "C49") (pin "1") (pinfunction "1_1") (pintype "passive"))
      (node (ref "C52") (pin "1") (pinfunction "1_1") (pintype "passive"))
      (node (ref "C7") (pin "1") (pinfunction "1_1") (pintype "passive"))
      (node (ref "C8") (pin "1") (pinfunction "1_1") (pintype "passive"))
      (node (ref "IC1") (pin "4") (pinfunction "FB_4") (pintype "input"))
      (node (ref "IC12") (pin "1") (pinfunction "+VS_1") (pintype "input"))
      (node (ref "IC13") (pin "1") (pinfunction "+VS_1") (pintype "input"))
      (node (ref "IC2") (pin "10") (pinfunction "SCL_10") (pintype "input"))
      (node (ref "IC2") (pin "16") (pinfunction "VCC_16") (pintype "power_in"))
      (node (ref "IC3") (pin "10") (pinfunction "SCL_10") (pintype "input"))
      (node (ref "IC3") (pin "16") (pinfunction "VCC_16") (pintype "power_in"))
      (node (ref "IC4") (pin "12") (pinfunction "VCC_12") (pintype "power_in"))
      (node (ref "ISP1") (pin "2") (pinfunction "VCC_2") (pintype "power_in"))
      (node (ref "ISP2") (pin "2") (pinfunction "VCC_2") (pintype "power_in"))
      (node (ref "ISP3") (pin "2") (pinfunction "VCC_2") (pintype "power_in"))
      (node (ref "ISP4") (pin "2") (pinfunction "VCC_2") (pintype "power_in"))
      (node (ref "ISP5") (pin "2") (pinfunction "VCC_2") (pintype "power_in"))
      (node (ref "L18") (pin "2") (pinfunction "2_2") (pintype "passive"))
      (node (ref "L2") (pin "P$1") (pinfunction "1_P$1") (pintype "passive"))
      (node (ref "L3") (pin "P$1") (pinfunction "1_P$1") (pintype "passive"))
      (node (ref "L4") (pin "P$1") (pinfunction "1_P$1") (pintype "passive"))
      (node (ref "LED3") (pin "A") (pinfunction "A_A") (pintype "passive"))
      (node (ref "R1") (pin "2") (pinfunction "2_2") (pintype "passive"))
      (node (ref "U2") (pin "1") (pinfunction "IN_1") (pintype "input"))
      (node (ref "U2") (pin "3") (pinfunction "EN_3") (pintype "input"))
      (node (ref "U3") (pin "18") (pinfunction "AVCC_18") (pintype "bidirectional"))
      (node (ref "U3") (pin "20") (pinfunction "AREF_20") (pintype "bidirectional"))
      (node (ref "U3") (pin "4") (pinfunction "VCC_4") (pintype "bidirectional"))
      (node (ref "U3") (pin "6") (pinfunction "VCC_6") (pintype "bidirectional"))
    )
    (net (code "2") (name "+12V") (class "Default")
      (node (ref "C1") (pin "+") (pinfunction "+_+") (pintype "passive"))
      (node (ref "C10") (pin "+") (pinfunction "+_+") (pintype "passive"))
      (node (ref "C11") (pin "1") (pinfunction "1_1") (pintype "passive"))
      (node (ref "C13") (pin "1") (pinfunction "1_1") (pintype "passive"))
      (node (ref "C14") (pin "+") (pinfunction "+_+") (pintype "passive"))
      (node (ref "C15") (pin "1") (pinfunction "1_1") (pintype "passive"))
      (node (ref "C17") (pin "1") (pinfunction "1_1") (pintype "passive"))
      (node (ref "C18") (pin "+") (pinfunction "+_+") (pintype "passive"))
      (node (ref "C19") (pin "1") (pinfunction "1_1") (pintype "passive"))
      (node (ref "C21") (pin "1") (pinfunction "1_1") (pintype "passive"))
      (node (ref "C38") (pin "1") (pinfunction "1_1") (pintype "passive"))
      (node (ref "C39") (pin "+") (pinfunction "+_+") (pintype "passive"))
      (node (ref "C4") (pin "+") (pinfunction "+_+") (pintype "passive"))
      (node (ref "C40") (pin "1") (pinfunction "1_1") (pintype "passive"))
      (node (ref "C42") (pin "1") (pinfunction "1_1") (pintype "passive"))
      (node (ref "C5") (pin "1") (pinfunction "1_1") (pintype "passive"))
      (node (ref "D10") (pin "C") (pinfunction "C_C") (pintype "passive"))
      (node (ref "D12") (pin "C") (pinfunction "C_C") (pintype "passive"))
      (node (ref "D14") (pin "C") (pinfunction "C_C") (pintype "passive"))
      (node (ref "D16") (pin "C") (pinfunction "C_C") (pintype "passive"))
      (node (ref "D18") (pin "C") (pinfunction "C_C") (pintype "passive"))
      (node (ref "D2") (pin "C") (pinfunction "C_C") (pintype "passive"))
      (node (ref "D20") (pin "C") (pinfunction "C_C") (pintype "passive"))
      (node (ref "D4") (pin "C") (pinfunction "C_C") (pintype "passive"))
      (node (ref "D6") (pin "C") (pinfunction "C_C") (pintype "passive"))
      (node (ref "D8") (pin "C") (pinfunction "C_C") (pintype "passive"))
      (node (ref "F5") (pin "2") (pinfunction "2_2") (pintype "bidirectional"))
      (node (ref "F6") (pin "2") (pinfunction "2_2") (pintype "bidirectional"))
      (node (ref "F7") (pin "2") (pinfunction "2_2") (pintype "bidirectional"))
      (node (ref "IC1") (pin "1") (pinfunction "IN_1") (pintype "input"))
      (node (ref "IC5") (pin "10") (pinfunction "VCC_10") (pintype "bidirectional"))
      (node (ref "IC5") (pin "19") (pinfunction "VCC_19") (pintype "bidirectional"))
      (node (ref "IC5") (pin "24") (pinfunction "VCC_24") (pintype "bidirectional"))
      (node (ref "IC5") (pin "5") (pinfunction "VCC_5") (pintype "bidirectional"))
      (node (ref "IC6") (pin "10") (pinfunction "VCC_10") (pintype "bidirectional"))
      (node (ref "IC6") (pin "19") (pinfunction "VCC_19") (pintype "bidirectional"))
      (node (ref "IC6") (pin "24") (pinfunction "VCC_24") (pintype "bidirectional"))
      (node (ref "IC6") (pin "5") (pinfunction "VCC_5") (pintype "bidirectional"))
      (node (ref "IC7") (pin "10") (pinfunction "VCC_10") (pintype "bidirectional"))
      (node (ref "IC7") (pin "19") (pinfunction "VCC_19") (pintype "bidirectional"))
      (node (ref "IC7") (pin "24") (pinfunction "VCC_24") (pintype "bidirectional"))
      (node (ref "IC7") (pin "5") (pinfunction "VCC_5") (pintype "bidirectional"))
      (node (ref "IC8") (pin "10") (pinfunction "VCC_10") (pintype "bidirectional"))
      (node (ref "IC8") (pin "19") (pinfunction "VCC_19") (pintype "bidirectional"))
      (node (ref "IC8") (pin "24") (pinfunction "VCC_24") (pintype "bidirectional"))
      (node (ref "IC8") (pin "5") (pinfunction "VCC_5") (pintype "bidirectional"))
      (node (ref "IC9") (pin "10") (pinfunction "VCC_10") (pintype "bidirectional"))
      (node (ref "IC9") (pin "19") (pinfunction "VCC_19") (pintype "bidirectional"))
      (node (ref "IC9") (pin "24") (pinfunction "VCC_24") (pintype "bidirectional"))
      (node (ref "IC9") (pin "5") (pinfunction "VCC_5") (pintype "bidirectional"))
      (node (ref "JP1") (pin "2") (pinfunction "2_2") (pintype "passive"))
      (node (ref "SJ1") (pin "2") (pinfunction "2_2") (pintype "passive"))
      (node (ref "SJ2") (pin "2") (pinfunction "2_2") (pintype "passive"))
      (node (ref "SJ3") (pin "2") (pinfunction "2_2") (pintype "passive"))
    )
    (net (code "3") (name "/0HA") (class "Default")
      (node (ref "IC6") (pin "2") (pinfunction "IN3_2") (pintype "bidirectional"))
      (node (ref "IC6") (pin "8") (pinfunction "IN1_8") (pintype "bidirectional"))
      (node (ref "R41") (pin "2") (pinfunction "1_2") (pintype "passive"))
    )
    (net (code "4") (name "/0HB") (class "Default")
      (node (ref "IC6") (pin "13") (pinfunction "IN4_13") (pintype "bidirectional"))
      (node (ref "IC6") (pin "7") (pinfunction "IN2_7") (pintype "bidirectional"))
      (node (ref "R41") (pin "1") (pinfunction "1_1") (pintype "passive"))
    )
    (net (code "5") (name "/0SENSE") (class "Default")
      (node (ref "R8") (pin "1") (pinfunction "1_1") (pintype "passive"))
      (node (ref "R9") (pin "1") (pinfunction "1_1") (pintype "passive"))
      (node (ref "U3") (pin "23") (pinfunction "PC0(ADC0)_23") (pintype "bidirectional"))
      (node (ref "ZD2") (pin "C") (pinfunction "C_C") (pintype "passive"))
    )
    (net (code "6") (name "/0STAT") (class "Default")
      (node (ref "IC6") (pin "4") (pinfunction "STAT3_4") (pintype "bidirectional"))
      (node (ref "U3") (pin "32") (pinfunction "PD2(INT0)_32") (pintype "bidirectional"))
    )
    (net (code "7") (name "/1HA") (class "Default")
      (node (ref "IC7") (pin "2") (pinfunction "IN3_2") (pintype "bidirectional"))
      (node (ref "IC7") (pin "8") (pinfunction "IN1_8") (pintype "bidirectional"))
      (node (ref "R41") (pin "3") (pinfunction "1_3") (pintype "passive"))
    )
    (net (code "8") (name "/1HB") (class "Default")
      (node (ref "IC7") (pin "13") (pinfunction "IN4_13") (pintype "bidirectional"))
      (node (ref "IC7") (pin "7") (pinfunction "IN2_7") (pintype "bidirectional"))
      (node (ref "R41") (pin "4") (pinfunction "1_4") (pintype "passive"))
    )
    (net (code "9") (name "/1SENSE") (class "Default")
      (node (ref "R10") (pin "1") (pinfunction "1_1") (pintype "passive"))
      (node (ref "R7") (pin "1") (pinfunction "1_1") (pintype "passive"))
      (node (ref "U3") (pin "24") (pinfunction "PC1(ADC1)_24") (pintype "bidirectional"))
      (node (ref "ZD3") (pin "C") (pinfunction "C_C") (pintype "passive"))
    )
    (net (code "10") (name "/1STAT") (class "Default")
      (node (ref "IC7") (pin "4") (pinfunction "STAT3_4") (pintype "bidirectional"))
      (node (ref "U3") (pin "1") (pinfunction "PD3(INT1)_1") (pintype "bidirectional"))
    )
    (net (code "11") (name "/2HA") (class "Default")
      (node (ref "IC5") (pin "2") (pinfunction "IN3_2") (pintype "bidirectional"))
      (node (ref "IC5") (pin "8") (pinfunction "IN1_8") (pintype "bidirectional"))
      (node (ref "R41") (pin "5") (pinfunction "1_5") (pintype "passive"))
    )
    (net (code "12") (name "/2HB") (class "Default")
      (node (ref "IC5") (pin "13") (pinfunction "IN4_13") (pintype "bidirectional"))
      (node (ref "IC5") (pin "7") (pinfunction "IN2_7") (pintype "bidirectional"))
      (node (ref "R41") (pin "6") (pinfunction "1_6") (pintype "passive"))
    )
    (net (code "13") (name "/2SENSE") (class "Default")
      (node (ref "R5") (pin "1") (pinfunction "1_1") (pintype "passive"))
      (node (ref "R6") (pin "1") (pinfunction "1_1") (pintype "passive"))
      (node (ref "U3") (pin "25") (pinfunction "PC2(ADC2)_25") (pintype "bidirectional"))
      (node (ref "ZD1") (pin "C") (pinfunction "C_C") (pintype "passive"))
    )
    (net (code "14") (name "/2STAT") (class "Default")
      (node (ref "IC5") (pin "4") (pinfunction "STAT3_4") (pintype "bidirectional"))
      (node (ref "U3") (pin "2") (pinfunction "PD4(XCK/T0)_2") (pintype "bidirectional"))
    )
    (net (code "15") (name "/3HA") (class "Default")
      (node (ref "IC9") (pin "2") (pinfunction "IN3_2") (pintype "bidirectional"))
      (node (ref "IC9") (pin "8") (pinfunction "IN1_8") (pintype "bidirectional"))
      (node (ref "R41") (pin "7") (pinfunction "1_7") (pintype "passive"))
    )
    (net (code "16") (name "/3HB") (class "Default")
      (node (ref "IC9") (pin "13") (pinfunction "IN4_13") (pintype "bidirectional"))
      (node (ref "IC9") (pin "7") (pinfunction "IN2_7") (pintype "bidirectional"))
      (node (ref "R41") (pin "8") (pinfunction "1_8") (pintype "passive"))
    )
    (net (code "17") (name "/3SENSE") (class "Default")
      (node (ref "R36") (pin "1") (pinfunction "1_1") (pintype "passive"))
      (node (ref "R37") (pin "1") (pinfunction "1_1") (pintype "passive"))
      (node (ref "U3") (pin "26") (pinfunction "PC3(ADC3)_26") (pintype "bidirectional"))
      (node (ref "ZD5") (pin "C") (pinfunction "C_C") (pintype "passive"))
    )
    (net (code "18") (name "/3STAT") (class "Default")
      (node (ref "IC9") (pin "4") (pinfunction "STAT3_4") (pintype "bidirectional"))
      (node (ref "U3") (pin "9") (pinfunction "PD5(T1)_9") (pintype "bidirectional"))
    )
    (net (code "19") (name "/4HA") (class "Default")
      (node (ref "IC8") (pin "2") (pinfunction "IN3_2") (pintype "bidirectional"))
      (node (ref "IC8") (pin "8") (pinfunction "IN1_8") (pintype "bidirectional"))
      (node (ref "R57") (pin "3") (pinfunction "1_3") (pintype "passive"))
    )
    (net (code "20") (name "/4HB") (class "Default")
      (node (ref "IC8") (pin "13") (pinfunction "IN4_13") (pintype "bidirectional"))
      (node (ref "IC8") (pin "7") (pinfunction "IN2_7") (pintype "bidirectional"))
      (node (ref "R57") (pin "1") (pinfunction "1_1") (pintype "passive"))
    )
    (net (code "21") (name "/4SENSE") (class "Default")
      (node (ref "R26") (pin "1") (pinfunction "1_1") (pintype "passive"))
      (node (ref "R31") (pin "1") (pinfunction "1_1") (pintype "passive"))
      (node (ref "U3") (pin "27") (pinfunction "PC4(ADC4/SDA)_27") (pintype "bidirectional"))
      (node (ref "ZD4") (pin "C") (pinfunction "C_C") (pintype "passive"))
    )
    (net (code "22") (name "/4STAT") (class "Default")
      (node (ref "IC8") (pin "4") (pinfunction "STAT3_4") (pintype "bidirectional"))
      (node (ref "U3") (pin "10") (pinfunction "PD6(AIN0)_10") (pintype "bidirectional"))
    )
    (net (code "23") (name "/D1+") (class "Default")
      (node (ref "C32") (pin "1") (pinfunction "1_1") (pintype "passive"))
      (node (ref "IC10") (pin "12") (pinfunction "D1+_12") (pintype "bidirectional"))
      (node (ref "R29") (pin "1") (pinfunction "1_1") (pintype "passive"))
    )
    (net (code "24") (name "/D1-") (class "Default")
      (node (ref "C33") (pin "1") (pinfunction "1_1") (pintype "passive"))
      (node (ref "IC10") (pin "11") (pinfunction "D1-_11") (pintype "bidirectional"))
      (node (ref "R28") (pin "1") (pinfunction "1_1") (pintype "passive"))
    )
    (net (code "25") (name "/ISP-MISO") (class "Default")
      (node (ref "ISP1") (pin "1") (pinfunction "MISO_1") (pintype "input"))
      (node (ref "R4") (pin "2") (pinfunction "2_2") (pintype "passive"))
      (node (ref "U3") (pin "16") (pinfunction "PB4(MISO)_16") (pintype "bidirectional"))
    )
    (net (code "26") (name "/ISP-MOSI") (class "Default")
      (node (ref "ISP1") (pin "4") (pinfunction "MOSI_4") (pintype "output"))
      (node (ref "R3") (pin "2") (pinfunction "2_2") (pintype "passive"))
      (node (ref "U3") (pin "15") (pinfunction "PB3(MOSI/OC2)_15") (pintype "bidirectional"))
    )
    (net (code "27") (name "/ISP-SCK") (class "Default")
      (node (ref "ISP1") (pin "3") (pinfunction "SCK_3") (pintype "output"))
      (node (ref "R2") (pin "2") (pinfunction "2_2") (pintype "passive"))
      (node (ref "U3") (pin "17") (pinfunction "PB5(SCK)_17") (pintype "bidirectional"))
    )
    (net (code "28") (name "/LATCH") (class "Default")
      (node (ref "IC2") (pin "12") (pinfunction "RCK_12") (pintype "input"))
      (node (ref "IC3") (pin "12") (pinfunction "RCK_12") (pintype "input"))
      (node (ref "U3") (pin "14") (pinfunction "PB2(SS/OC1B)_14") (pintype "bidirectional"))
    )
    (net (code "29") (name "/MISO") (class "Default")
      (node (ref "ISP2") (pin "1") (pinfunction "MISO_1") (pintype "input"))
      (node (ref "ISP3") (pin "1") (pinfunction "MISO_1") (pintype "input"))
      (node (ref "ISP4") (pin "1") (pinfunction "MISO_1") (pintype "input"))
      (node (ref "ISP5") (pin "1") (pinfunction "MISO_1") (pintype "input"))
      (node (ref "R4") (pin "1") (pinfunction "1_1") (pintype "passive"))
    )
    (net (code "30") (name "/MOSI") (class "Default")
      (node (ref "IC2") (pin "14") (pinfunction "SER_14") (pintype "input"))
      (node (ref "ISP2") (pin "4") (pinfunction "MOSI_4") (pintype "output"))
      (node (ref "ISP3") (pin "4") (pinfunction "MOSI_4") (pintype "output"))
      (node (ref "ISP4") (pin "4") (pinfunction "MOSI_4") (pintype "output"))
      (node (ref "ISP5") (pin "4") (pinfunction "MOSI_4") (pintype "output"))
      (node (ref "R3") (pin "1") (pinfunction "1_1") (pintype "passive"))
    )
    (net (code "31") (name "/RXD") (class "Default")
      (node (ref "IC4") (pin "1") (pinfunction "TXD_1") (pintype "output"))
      (node (ref "U3") (pin "30") (pinfunction "PD0(RXD)_30") (pintype "bidirectional"))
    )
    (net (code "32") (name "/SCK") (class "Default")
      (node (ref "IC2") (pin "11") (pinfunction "SCK_11") (pintype "input"))
      (node (ref "IC3") (pin "11") (pinfunction "SCK_11") (pintype "input"))
      (node (ref "ISP2") (pin "3") (pinfunction "SCK_3") (pintype "output"))
      (node (ref "ISP3") (pin "3") (pinfunction "SCK_3") (pintype "output"))
      (node (ref "ISP4") (pin "3") (pinfunction "SCK_3") (pintype "output"))
      (node (ref "ISP5") (pin "3") (pinfunction "SCK_3") (pintype "output"))
      (node (ref "R2") (pin "1") (pinfunction "1_1") (pintype "passive"))
    )
    (net (code "33") (name "/SW0") (class "Default")
      (node (ref "Q3") (pin "1") (pinfunction "G_1") (pintype "bidirectional"))
      (node (ref "R57") (pin "2") (pinfunction "1_2") (pintype "passive"))
    )
    (net (code "34") (name "/SW1") (class "Default")
      (node (ref "Q2") (pin "1") (pinfunction "G_1") (pintype "bidirectional"))
      (node (ref "R57") (pin "4") (pinfunction "1_4") (pintype "passive"))
    )
    (net (code "35") (name "/SW2") (class "Default")
      (node (ref "Q1") (pin "1") (pinfunction "G_1") (pintype "bidirectional"))
      (node (ref "R57") (pin "5") (pinfunction "1_5") (pintype "passive"))
    )
    (net (code "36") (name "/SW3") (class "Default")
      (node (ref "JP12") (pin "1") (pinfunction "1_1") (pintype "passive"))
      (node (ref "R57") (pin "6") (pinfunction "1_6") (pintype "passive"))
    )
    (net (code "37") (name "/SW4") (class "Default")
      (node (ref "JP12") (pin "2") (pinfunction "2_2") (pintype "passive"))
      (node (ref "R57") (pin "7") (pinfunction "1_7") (pintype "passive"))
    )
    (net (code "38") (name "/SW5") (class "Default")
      (node (ref "JP12") (pin "3") (pinfunction "3_3") (pintype "passive"))
      (node (ref "R57") (pin "8") (pinfunction "1_8") (pintype "passive"))
    )
    (net (code "39") (name "/TEMP0") (class "Default")
      (node (ref "C50") (pin "1") (pinfunction "1_1") (pintype "passive"))
      (node (ref "IC12") (pin "2") (pinfunction "VO_2") (pintype "input"))
      (node (ref "U3") (pin "28") (pinfunction "PC5(ADC5/SCL)_28") (pintype "bidirectional"))
    )
    (net (code "40") (name "/TEMP1") (class "Default")
      (node (ref "C51") (pin "1") (pinfunction "1_1") (pintype "passive"))
      (node (ref "IC13") (pin "2") (pinfunction "VO_2") (pintype "input"))
      (node (ref "U3") (pin "19") (pinfunction "ADC6_19") (pintype "bidirectional"))
    )
    (net (code "41") (name "/TXD") (class "Default")
      (node (ref "IC4") (pin "4") (pinfunction "RXD_4") (pintype "input"))
      (node (ref "U3") (pin "31") (pinfunction "PD1(TXD)_31") (pintype "bidirectional"))
    )
    (net (code "42") (name "/~{EN1}") (class "Default")
      (node (ref "R39") (pin "2") (pinfunction "2_2") (pintype "passive"))
      (node (ref "U3") (pin "22") (pinfunction "ADC7_22") (pintype "bidirectional"))
    )
    (net (code "43") (name "/~{EN2}") (class "Default")
      (node (ref "R38") (pin "2") (pinfunction "2_2") (pintype "passive"))
      (node (ref "U3") (pin "11") (pinfunction "PD7(AIN1)_11") (pintype "bidirectional"))
    )
    (net (code "44") (name "/~{EN3}") (class "Default")
      (node (ref "R33") (pin "2") (pinfunction "2_2") (pintype "passive"))
      (node (ref "U3") (pin "12") (pinfunction "PB0(ICP)_12") (pintype "bidirectional"))
    )
    (net (code "45") (name "/~{EN4}") (class "Default")
      (node (ref "R32") (pin "2") (pinfunction "2_2") (pintype "passive"))
      (node (ref "U3") (pin "13") (pinfunction "PB1(OC1A)_13") (pintype "bidirectional"))
    )
    (net (code "46") (name "/~{RST}") (class "Default")
      (node (ref "C43") (pin "1") (pinfunction "1_1") (pintype "passive"))
      (node (ref "ISP1") (pin "5") (pinfunction "RST_5") (pintype "output"))
      (node (ref "R1") (pin "1") (pinfunction "1_1") (pintype "passive"))
      (node (ref "SW1") (pin "B") (pinfunction "S_B") (pintype "passive"))
      (node (ref "U3") (pin "29") (pinfunction "PC6(/RESET)_29") (pintype "bidirectional"))
    )
    (net (code "47") (name "3.3V") (class "Default")
      (node (ref "C35") (pin "1") (pinfunction "1_1") (pintype "passive"))
      (node (ref "C36") (pin "1") (pinfunction "1_1") (pintype "passive"))
      (node (ref "IC10") (pin "10") (pinfunction "~{OVRCUR1}_10") (pintype "bidirectional"))
      (node (ref "IC10") (pin "14") (pinfunction "~{OVRCUR2}_14") (pintype "bidirectional"))
      (node (ref "IC10") (pin "18") (pinfunction "~{OVRCUR3}_18") (pintype "bidirectional"))
      (node (ref "IC10") (pin "22") (pinfunction "~{OVRCUR4}_22") (pintype "bidirectional"))
      (node (ref "IC10") (pin "25") (pinfunction "VCC_25") (pintype "bidirectional"))
      (node (ref "IC10") (pin "26") (pinfunction "~{EXTMEM}_26") (pintype "bidirectional"))
      (node (ref "IC10") (pin "3") (pinfunction "VCC_3") (pintype "bidirectional"))
      (node (ref "IC10") (pin "4") (pinfunction "~{RST}_4") (pintype "bidirectional"))
      (node (ref "R11") (pin "2") (pinfunction "2_2") (pintype "passive"))
      (node (ref "U2") (pin "5") (pinfunction "OUT_5") (pintype "passive"))
    )
    (net (code "48") (name "AGND") (class "Default")
      (node (ref "C44") (pin "2") (pinfunction "2_2") (pintype "passive"))
      (node (ref "C46") (pin "2") (pinfunction "2_2") (pintype "passive"))
      (node (ref "C47") (pin "2") (pinfunction "2_2") (pintype "passive"))
      (node (ref "C48") (pin "2") (pinfunction "2_2") (pintype "passive"))
      (node (ref "C49") (pin "2") (pinfunction "2_2") (pintype "passive"))
      (node (ref "C50") (pin "2") (pinfunction "2_2") (pintype "passive"))
      (node (ref "C51") (pin "2") (pinfunction "2_2") (pintype "passive"))
      (node (ref "IC12") (pin "3") (pinfunction "GND_3") (pintype "power_in"))
      (node (ref "IC13") (pin "3") (pinfunction "GND_3") (pintype "power_in"))
      (node (ref "R10") (pin "2") (pinfunction "2_2") (pintype "passive"))
      (node (ref "R31") (pin "2") (pinfunction "2_2") (pintype "passive"))
      (node (ref "R35") (pin "1") (pinfunction "1_1") (pintype "passive"))
      (node (ref "R37") (pin "2") (pinfunction "2_2") (pintype "passive"))
      (node (ref "R5") (pin "2") (pinfunction "2_2") (pintype "passive"))
      (node (ref "R8") (pin "2") (pinfunction "2_2") (pintype "passive"))
      (node (ref "U3") (pin "5") (pinfunction "AGND_5") (pintype "bidirectional"))
      (node (ref "ZD1") (pin "A") (pinfunction "A_A") (pintype "passive"))
      (node (ref "ZD2") (pin "A") (pinfunction "A_A") (pintype "passive"))
      (node (ref "ZD3") (pin "A") (pinfunction "A_A") (pintype "passive"))
      (node (ref "ZD4") (pin "A") (pinfunction "A_A") (pintype "passive"))
      (node (ref "ZD5") (pin "A") (pinfunction "A_A") (pintype "passive"))
    )
    (net (code "49") (name "GND") (class "Default")
      (node (ref "C1") (pin "-") (pinfunction "-_-") (pintype "passive"))
      (node (ref "C10") (pin "-") (pinfunction "-_-") (pintype "passive"))
      (node (ref "C11") (pin "2") (pinfunction "2_2") (pintype "passive"))
      (node (ref "C13") (pin "2") (pinfunction "2_2") (pintype "passive"))
      (node (ref "C14") (pin "-") (pinfunction "-_-") (pintype "passive"))
      (node (ref "C15") (pin "2") (pinfunction "2_2") (pintype "passive"))
      (node (ref "C17") (pin "2") (pinfunction "2_2") (pintype "passive"))
      (node (ref "C18") (pin "-") (pinfunction "-_-") (pintype "passive"))
      (node (ref "C19") (pin "2") (pinfunction "2_2") (pintype "passive"))
      (node (ref "C2") (pin "-") (pinfunction "-_-") (pintype "passive"))
      (node (ref "C21") (pin "2") (pinfunction "2_2") (pintype "passive"))
      (node (ref "C22") (pin "2") (pinfunction "2_2") (pintype "passive"))
      (node (ref "C23") (pin "2") (pinfunction "2_2") (pintype "passive"))
      (node (ref "C24") (pin "2") (pinfunction "2_2") (pintype "passive"))
      (node (ref "C25") (pin "2") (pinfunction "2_2") (pintype "passive"))
      (node (ref "C26") (pin "2") (pinfunction "2_2") (pintype "passive"))
      (node (ref "C27") (pin "2") (pinfunction "2_2") (pintype "passive"))
      (node (ref "C28") (pin "2") (pinfunction "2_2") (pintype "passive"))
      (node (ref "C29") (pin "2") (pinfunction "2_2") (pintype "passive"))
      (node (ref "C3") (pin "2") (pinfunction "2_2") (pintype "passive"))
      (node (ref "C30") (pin "2") (pinfunction "2_2") (pintype "passive"))
      (node (ref "C31") (pin "2") (pinfunction "2_2") (pintype "passive"))
      (node (ref "C32") (pin "2") (pinfunction "2_2") (pintype "passive"))
      (node (ref "C33") (pin "2") (pinfunction "2_2") (pintype "passive"))
      (node (ref "C34") (pin "2") (pinfunction "2_2") (pintype "passive"))
      (node (ref "C35") (pin "2") (pinfunction "2_2") (pintype "passive"))
      (node (ref "C36") (pin "2") (pinfunction "2_2") (pintype "passive"))
      (node (ref "C37") (pin "2") (pinfunction "2_2") (pintype "passive"))
      (node (ref "C38") (pin "2") (pinfunction "2_2") (pintype "passive"))
      (node (ref "C39") (pin "-") (pinfunction "-_-") (pintype "passive"))
      (node (ref "C4") (pin "-") (pinfunction "-_-") (pintype "passive"))
      (node (ref "C40") (pin "2") (pinfunction "2_2") (pintype "passive"))
      (node (ref "C42") (pin "2") (pinfunction "2_2") (pintype "passive"))
      (node (ref "C5") (pin "2") (pinfunction "2_2") (pintype "passive"))
      (node (ref "C52") (pin "2") (pinfunction "2_2") (pintype "passive"))
      (node (ref "C53") (pin "-") (pinfunction "-_-") (pintype "passive"))
      (node (ref "C54") (pin "-") (pinfunction "-_-") (pintype "passive"))
      (node (ref "C55") (pin "-") (pinfunction "-_-") (pintype "passive"))
      (node (ref "C7") (pin "2") (pinfunction "2_2") (pintype "passive"))
      (node (ref "C8") (pin "2") (pinfunction "2_2") (pintype "passive"))
      (node (ref "C9") (pin "2") (pinfunction "2_2") (pintype "passive"))
      (node (ref "D1") (pin "A") (pinfunction "A_A") (pintype "passive"))
      (node (ref "D11") (pin "A") (pinfunction "A_A") (pintype "passive"))
      (node (ref "D13") (pin "A") (pinfunction "A_A") (pintype "passive"))
      (node (ref "D15") (pin "A") (pinfunction "A_A") (pintype "passive"))
      (node (ref "D17") (pin "A") (pinfunction "A_A") (pintype "passive"))
      (node (ref "D19") (pin "A") (pinfunction "A_A") (pintype "passive"))
      (node (ref "D21") (pin "A") (pinfunction "A_A") (pintype "passive"))
      (node (ref "D3") (pin "A") (pinfunction "A_A") (pintype "passive"))
      (node (ref "D5") (pin "A") (pinfunction "A_A") (pintype "passive"))
      (node (ref "D7") (pin "A") (pinfunction "A_A") (pintype "passive"))
      (node (ref "D9") (pin "A") (pinfunction "A_A") (pintype "passive"))
      (node (ref "IC1") (pin "3") (pinfunction "GND_3") (pintype "power_in"))
      (node (ref "IC1") (pin "5") (pinfunction "EN_5") (pintype "input"))
      (node (ref "IC1") (pin "6") (pinfunction "GND_6") (pintype "power_in"))
      (node (ref "IC10") (pin "27") (pinfunction "PLL/48M_27") (pintype "bidirectional"))
      (node (ref "IC10") (pin "28") (pinfunction "GND_28") (pintype "bidirectional"))
      (node (ref "IC10") (pin "31") (pinfunction "TSTMODE_31") (pintype "bidirectional"))
      (node (ref "IC10") (pin "6") (pinfunction "EEDATA/GANGED_6") (pintype "bidirectional"))
      (node (ref "IC10") (pin "7") (pinfunction "GND_7") (pintype "bidirectional"))
      (node (ref "IC10") (pin "8") (pinfunction "BUSPWR_8") (pintype "bidirectional"))
      (node (ref "IC2") (pin "13") (pinfunction "G_13") (pintype "input"))
      (node (ref "IC2") (pin "8") (pinfunction "GND_8") (pintype "power_in"))
      (node (ref "IC3") (pin "13") (pinfunction "G_13") (pintype "input"))
      (node (ref "IC3") (pin "8") (pinfunction "GND_8") (pintype "power_in"))
      (node (ref "IC4") (pin "13") (pinfunction "GND_13") (pintype "power_in"))
      (node (ref "IC4") (pin "5") (pinfunction "GND_5") (pintype "power_in"))
      (node (ref "IC5") (pin "16") (pinfunction "SOURCE4_16") (pintype "bidirectional"))
      (node (ref "IC5") (pin "17") (pinfunction "SOURCE4_17") (pintype "bidirectional"))
      (node (ref "IC5") (pin "26") (pinfunction "SOURCE3_26") (pintype "bidirectional"))
      (node (ref "IC5") (pin "27") (pinfunction "SOURCE3_27") (pintype "bidirectional"))
      (node (ref "IC5") (pin "6") (pinfunction "GND_6") (pintype "bidirectional"))
      (node (ref "IC6") (pin "16") (pinfunction "SOURCE4_16") (pintype "bidirectional"))
      (node (ref "IC6") (pin "17") (pinfunction "SOURCE4_17") (pintype "bidirectional"))
      (node (ref "IC6") (pin "26") (pinfunction "SOURCE3_26") (pintype "bidirectional"))
      (node (ref "IC6") (pin "27") (pinfunction "SOURCE3_27") (pintype "bidirectional"))
      (node (ref "IC6") (pin "6") (pinfunction "GND_6") (pintype "bidirectional"))
      (node (ref "IC7") (pin "16") (pinfunction "SOURCE4_16") (pintype "bidirectional"))
      (node (ref "IC7") (pin "17") (pinfunction "SOURCE4_17") (pintype "bidirectional"))
      (node (ref "IC7") (pin "26") (pinfunction "SOURCE3_26") (pintype "bidirectional"))
      (node (ref "IC7") (pin "27") (pinfunction "SOURCE3_27") (pintype "bidirectional"))
      (node (ref "IC7") (pin "6") (pinfunction "GND_6") (pintype "bidirectional"))
      (node (ref "IC8") (pin "16") (pinfunction "SOURCE4_16") (pintype "bidirectional"))
      (node (ref "IC8") (pin "17") (pinfunction "SOURCE4_17") (pintype "bidirectional"))
      (node (ref "IC8") (pin "26") (pinfunction "SOURCE3_26") (pintype "bidirectional"))
      (node (ref "IC8") (pin "27") (pinfunction "SOURCE3_27") (pintype "bidirectional"))
      (node (ref "IC8") (pin "6") (pinfunction "GND_6") (pintype "bidirectional"))
      (node (ref "IC9") (pin "16") (pinfunction "SOURCE4_16") (pintype "bidirectional"))
      (node (ref "IC9") (pin "17") (pinfunction "SOURCE4_17") (pintype "bidirectional"))
      (node (ref "IC9") (pin "26") (pinfunction "SOURCE3_26") (pintype "bidirectional"))
      (node (ref "IC9") (pin "27") (pinfunction "SOURCE3_27") (pintype "bidirectional"))
      (node (ref "IC9") (pin "6") (pinfunction "GND_6") (pintype "bidirectional"))
      (node (ref "ISP1") (pin "6") (pinfunction "GND_6") (pintype "power_in"))
      (node (ref "ISP2") (pin "6") (pinfunction "GND_6") (pintype "power_in"))
      (node (ref "ISP3") (pin "6") (pinfunction "GND_6") (pintype "power_in"))
      (node (ref "ISP4") (pin "6") (pinfunction "GND_6") (pintype "power_in"))
      (node (ref "ISP5") (pin "6") (pinfunction "GND_6") (pintype "power_in"))
      (node (ref "JP1") (pin "1") (pinfunction "1_1") (pintype "passive"))
      (node (ref "JP11") (pin "1") (pinfunction "1_1") (pintype "passive"))
      (node (ref "JP13") (pin "1") (pinfunction "1_1") (pintype "passive"))
      (node (ref "JP17") (pin "1") (pinfunction "1_1") (pintype "passive"))
      (node (ref "Q1") (pin "2") (pinfunction "S_2") (pintype "bidirectional"))
      (node (ref "Q2") (pin "2") (pinfunction "S_2") (pintype "bidirectional"))
      (node (ref "Q3") (pin "2") (pinfunction "S_2") (pintype "bidirectional"))
      (node (ref "R14") (pin "2") (pinfunction "2_2") (pintype "passive"))
      (node (ref "R15") (pin "2") (pinfunction "2_2") (pintype "passive"))
      (node (ref "R22") (pin "2") (pinfunction "2_2") (pintype "passive"))
      (node (ref "R23") (pin "2") (pinfunction "2_2") (pintype "passive"))
      (node (ref "R24") (pin "2") (pinfunction "2_2") (pintype "passive"))
      (node (ref "R25") (pin "2") (pinfunction "2_2") (pintype "passive"))
      (node (ref "R27") (pin "1") (pinfunction "1_1") (pintype "passive"))
      (node (ref "R30") (pin "1") (pinfunction "1_1") (pintype "passive"))
      (node (ref "R34") (pin "2") (pinfunction "2_2") (pintype "passive"))
      (node (ref "R35") (pin "2") (pinfunction "2_2") (pintype "passive"))
      (node (ref "SW1") (pin "A") (pinfunction "P_A") (pintype "passive"))
      (node (ref "U$6") (pin "A") (pinfunction "1_A") (pintype "passive"))
      (node (ref "U$7") (pin "A") (pinfunction "1_A") (pintype "passive"))
      (node (ref "U$8") (pin "A") (pinfunction "1_A") (pintype "passive"))
      (node (ref "U2") (pin "2") (pinfunction "GND_2") (pintype "input"))
      (node (ref "U3") (pin "21") (pinfunction "GND_21") (pintype "bidirectional"))
      (node (ref "U3") (pin "3") (pinfunction "GND_3") (pintype "bidirectional"))
      (node (ref "Y1") (pin "2") (pinfunction "2_2") (pintype "passive"))
      (node (ref "Y2") (pin "2") (pinfunction "2_2") (pintype "passive"))
    )
    (net (code "50") (name "Net-(C6-Pad1)") (class "Default")
      (node (ref "C6") (pin "1") (pinfunction "1_1") (pintype "passive"))
      (node (ref "D2") (pin "A") (pinfunction "A_A") (pintype "passive"))
      (node (ref "D3") (pin "C") (pinfunction "C_C") (pintype "passive"))
      (node (ref "IC5") (pin "1") (pinfunction "DRAIN3_1") (pintype "bidirectional"))
      (node (ref "IC5") (pin "22") (pinfunction "SOURCE2_22") (pintype "bidirectional"))
      (node (ref "IC5") (pin "23") (pinfunction "SOURCE2_23") (pintype "bidirectional"))
      (node (ref "IC5") (pin "25") (pinfunction "DRAIN3_25") (pintype "bidirectional"))
      (node (ref "IC5") (pin "28") (pinfunction "DRAIN3_28") (pintype "bidirectional"))
      (node (ref "IC5") (pin "3") (pinfunction "DRAIN3_3") (pintype "bidirectional"))
      (node (ref "JP2") (pin "2") (pinfunction "2_2") (pintype "passive"))
    )
    (net (code "51") (name "Net-(C6-Pad2)") (class "Default")
      (node (ref "C6") (pin "2") (pinfunction "2_2") (pintype "passive"))
      (node (ref "D4") (pin "A") (pinfunction "A_A") (pintype "passive"))
      (node (ref "D5") (pin "C") (pinfunction "C_C") (pintype "passive"))
      (node (ref "IC5") (pin "12") (pinfunction "DRAIN4_12") (pintype "bidirectional"))
      (node (ref "IC5") (pin "14") (pinfunction "DRAIN4_14") (pintype "bidirectional"))
      (node (ref "IC5") (pin "15") (pinfunction "DRAIN4_15") (pintype "bidirectional"))
      (node (ref "IC5") (pin "18") (pinfunction "DRAIN4_18") (pintype "bidirectional"))
      (node (ref "IC5") (pin "20") (pinfunction "SOURCE1_20") (pintype "bidirectional"))
      (node (ref "IC5") (pin "21") (pinfunction "SOURCE1_21") (pintype "bidirectional"))
      (node (ref "JP2") (pin "1") (pinfunction "1_1") (pintype "passive"))
    )
    (net (code "52") (name "Net-(C12-Pad1)") (class "Default")
      (node (ref "C12") (pin "1") (pinfunction "1_1") (pintype "passive"))
      (node (ref "D6") (pin "A") (pinfunction "A_A") (pintype "passive"))
      (node (ref "D7") (pin "C") (pinfunction "C_C") (pintype "passive"))
      (node (ref "IC6") (pin "1") (pinfunction "DRAIN3_1") (pintype "bidirectional"))
      (node (ref "IC6") (pin "22") (pinfunction "SOURCE2_22") (pintype "bidirectional"))
      (node (ref "IC6") (pin "23") (pinfunction "SOURCE2_23") (pintype "bidirectional"))
      (node (ref "IC6") (pin "25") (pinfunction "DRAIN3_25") (pintype "bidirectional"))
      (node (ref "IC6") (pin "28") (pinfunction "DRAIN3_28") (pintype "bidirectional"))
      (node (ref "IC6") (pin "3") (pinfunction "DRAIN3_3") (pintype "bidirectional"))
      (node (ref "JP3") (pin "2") (pinfunction "2_2") (pintype "passive"))
    )
    (net (code "53") (name "Net-(C12-Pad2)") (class "Default")
      (node (ref "C12") (pin "2") (pinfunction "2_2") (pintype "passive"))
      (node (ref "D8") (pin "A") (pinfunction "A_A") (pintype "passive"))
      (node (ref "D9") (pin "C") (pinfunction "C_C") (pintype "passive"))
      (node (ref "IC6") (pin "12") (pinfunction "DRAIN4_12") (pintype "bidirectional"))
      (node (ref "IC6") (pin "14") (pinfunction "DRAIN4_14") (pintype "bidirectional"))
      (node (ref "IC6") (pin "15") (pinfunction "DRAIN4_15") (pintype "bidirectional"))
      (node (ref "IC6") (pin "18") (pinfunction "DRAIN4_18") (pintype "bidirectional"))
      (node (ref "IC6") (pin "20") (pinfunction "SOURCE1_20") (pintype "bidirectional"))
      (node (ref "IC6") (pin "21") (pinfunction "SOURCE1_21") (pintype "bidirectional"))
      (node (ref "JP3") (pin "1") (pinfunction "1_1") (pintype "passive"))
    )
    (net (code "54") (name "Net-(C16-Pad1)") (class "Default")
      (node (ref "C16") (pin "1") (pinfunction "1_1") (pintype "passive"))
      (node (ref "D10") (pin "A") (pinfunction "A_A") (pintype "passive"))
      (node (ref "D11") (pin "C") (pinfunction "C_C") (pintype "passive"))
      (node (ref "IC7") (pin "1") (pinfunction "DRAIN3_1") (pintype "bidirectional"))
      (node (ref "IC7") (pin "22") (pinfunction "SOURCE2_22") (pintype "bidirectional"))
      (node (ref "IC7") (pin "23") (pinfunction "SOURCE2_23") (pintype "bidirectional"))
      (node (ref "IC7") (pin "25") (pinfunction "DRAIN3_25") (pintype "bidirectional"))
      (node (ref "IC7") (pin "28") (pinfunction "DRAIN3_28") (pintype "bidirectional"))
      (node (ref "IC7") (pin "3") (pinfunction "DRAIN3_3") (pintype "bidirectional"))
      (node (ref "JP4") (pin "2") (pinfunction "2_2") (pintype "passive"))
    )
    (net (code "55") (name "Net-(C16-Pad2)") (class "Default")
      (node (ref "C16") (pin "2") (pinfunction "2_2") (pintype "passive"))
      (node (ref "D12") (pin "A") (pinfunction "A_A") (pintype "passive"))
      (node (ref "D13") (pin "C") (pinfunction "C_C") (pintype "passive"))
      (node (ref "IC7") (pin "12") (pinfunction "DRAIN4_12") (pintype "bidirectional"))
      (node (ref "IC7") (pin "14") (pinfunction "DRAIN4_14") (pintype "bidirectional"))
      (node (ref "IC7") (pin "15") (pinfunction "DRAIN4_15") (pintype "bidirectional"))
      (node (ref "IC7") (pin "18") (pinfunction "DRAIN4_18") (pintype "bidirectional"))
      (node (ref "IC7") (pin "20") (pinfunction "SOURCE1_20") (pintype "bidirectional"))
      (node (ref "IC7") (pin "21") (pinfunction "SOURCE1_21") (pintype "bidirectional"))
      (node (ref "JP4") (pin "1") (pinfunction "1_1") (pintype "passive"))
    )
    (net (code "56") (name "Net-(C20-Pad1)") (class "Default")
      (node (ref "C20") (pin "1") (pinfunction "1_1") (pintype "passive"))
      (node (ref "D14") (pin "A") (pinfunction "A_A") (pintype "passive"))
      (node (ref "D15") (pin "C") (pinfunction "C_C") (pintype "passive"))
      (node (ref "IC8") (pin "1") (pinfunction "DRAIN3_1") (pintype "bidirectional"))
      (node (ref "IC8") (pin "22") (pinfunction "SOURCE2_22") (pintype "bidirectional"))
      (node (ref "IC8") (pin "23") (pinfunction "SOURCE2_23") (pintype "bidirectional"))
      (node (ref "IC8") (pin "25") (pinfunction "DRAIN3_25") (pintype "bidirectional"))
      (node (ref "IC8") (pin "28") (pinfunction "DRAIN3_28") (pintype "bidirectional"))
      (node (ref "IC8") (pin "3") (pinfunction "DRAIN3_3") (pintype "bidirectional"))
      (node (ref "JP5") (pin "2") (pinfunction "2_2") (pintype "passive"))
    )
    (net (code "57") (name "Net-(C20-Pad2)") (class "Default")
      (node (ref "C20") (pin "2") (pinfunction "2_2") (pintype "passive"))
      (node (ref "D16") (pin "A") (pinfunction "A_A") (pintype "passive"))
      (node (ref "D17") (pin "C") (pinfunction "C_C") (pintype "passive"))
      (node (ref "IC8") (pin "12") (pinfunction "DRAIN4_12") (pintype "bidirectional"))
      (node (ref "IC8") (pin "14") (pinfunction "DRAIN4_14") (pintype "bidirectional"))
      (node (ref "IC8") (pin "15") (pinfunction "DRAIN4_15") (pintype "bidirectional"))
      (node (ref "IC8") (pin "18") (pinfunction "DRAIN4_18") (pintype "bidirectional"))
      (node (ref "IC8") (pin "20") (pinfunction "SOURCE1_20") (pintype "bidirectional"))
      (node (ref "IC8") (pin "21") (pinfunction "SOURCE1_21") (pintype "bidirectional"))
      (node (ref "JP5") (pin "1") (pinfunction "1_1") (pintype "passive"))
    )
    (net (code "58") (name "Net-(C41-Pad1)") (class "Default")
      (node (ref "C41") (pin "1") (pinfunction "1_1") (pintype "passive"))
      (node (ref "D18") (pin "A") (pinfunction "A_A") (pintype "passive"))
      (node (ref "D19") (pin "C") (pinfunction "C_C") (pintype "passive"))
      (node (ref "IC9") (pin "1") (pinfunction "DRAIN3_1") (pintype "bidirectional"))
      (node (ref "IC9") (pin "22") (pinfunction "SOURCE2_22") (pintype "bidirectional"))
      (node (ref "IC9") (pin "23") (pinfunction "SOURCE2_23") (pintype "bidirectional"))
      (node (ref "IC9") (pin "25") (pinfunction "DRAIN3_25") (pintype "bidirectional"))
      (node (ref "IC9") (pin "28") (pinfunction "DRAIN3_28") (pintype "bidirectional"))
      (node (ref "IC9") (pin "3") (pinfunction "DRAIN3_3") (pintype "bidirectional"))
      (node (ref "JP6") (pin "2") (pinfunction "2_2") (pintype "passive"))
    )
    (net (code "59") (name "Net-(C41-Pad2)") (class "Default")
      (node (ref "C41") (pin "2") (pinfunction "2_2") (pintype "passive"))
      (node (ref "D20") (pin "A") (pinfunction "A_A") (pintype "passive"))
      (node (ref "D21") (pin "C") (pinfunction "C_C") (pintype "passive"))
      (node (ref "IC9") (pin "12") (pinfunction "DRAIN4_12") (pintype "bidirectional"))
      (node (ref "IC9") (pin "14") (pinfunction "DRAIN4_14") (pintype "bidirectional"))
      (node (ref "IC9") (pin "15") (pinfunction "DRAIN4_15") (pintype "bidirectional"))
      (node (ref "IC9") (pin "18") (pinfunction "DRAIN4_18") (pintype "bidirectional"))
      (node (ref "IC9") (pin "20") (pinfunction "SOURCE1_20") (pintype "bidirectional"))
      (node (ref "IC9") (pin "21") (pinfunction "SOURCE1_21") (pintype "bidirectional"))
      (node (ref "JP6") (pin "1") (pinfunction "1_1") (pintype "passive"))
    )
    (net (code "60") (name "Net-(F1-Pad2)") (class "Default")
      (node (ref "F1") (pin "2") (pinfunction "2_2") (pintype "passive"))
      (node (ref "JP17") (pin "4") (pinfunction "4_4") (pintype "passive"))
    )
    (net (code "61") (name "Net-(F2-Pad2)") (class "Default")
      (node (ref "F2") (pin "2") (pinfunction "2_2") (pintype "passive"))
      (node (ref "JP13") (pin "4") (pinfunction "4_4") (pintype "passive"))
    )
    (net (code "62") (name "Net-(F3-Pad2)") (class "Default")
      (node (ref "F3") (pin "2") (pinfunction "2_2") (pintype "passive"))
      (node (ref "JP11") (pin "4") (pinfunction "4_4") (pintype "passive"))
    )
    (net (code "63") (name "Net-(IC1-OUT)") (class "Default")
      (node (ref "D1") (pin "C") (pinfunction "C_C") (pintype "passive"))
      (node (ref "IC1") (pin "2") (pinfunction "OUT_2") (pintype "output"))
      (node (ref "L18") (pin "1") (pinfunction "1_1") (pintype "passive"))
    )
    (net (code "64") (name "Net-(IC2-QA)") (class "Default")
      (node (ref "IC2") (pin "15") (pinfunction "QA_15") (pintype "tri_state"))
      (node (ref "R41") (pin "15") (pinfunction "2_15") (pintype "passive"))
    )
    (net (code "65") (name "Net-(IC2-QB)") (class "Default")
      (node (ref "IC2") (pin "1") (pinfunction "QB_1") (pintype "tri_state"))
      (node (ref "R41") (pin "16") (pinfunction "2_16") (pintype "passive"))
    )
    (net (code "66") (name "Net-(IC2-QC)") (class "Default")
      (node (ref "IC2") (pin "2") (pinfunction "QC_2") (pintype "tri_state"))
      (node (ref "R41") (pin "14") (pinfunction "2_14") (pintype "passive"))
    )
    (net (code "67") (name "Net-(IC2-QD)") (class "Default")
      (node (ref "IC2") (pin "3") (pinfunction "QD_3") (pintype "tri_state"))
      (node (ref "R41") (pin "13") (pinfunction "2_13") (pintype "passive"))
    )
    (net (code "68") (name "Net-(IC2-QE)") (class "Default")
      (node (ref "IC2") (pin "4") (pinfunction "QE_4") (pintype "tri_state"))
      (node (ref "R41") (pin "12") (pinfunction "2_12") (pintype "passive"))
    )
    (net (code "69") (name "Net-(IC2-QF)") (class "Default")
      (node (ref "IC2") (pin "5") (pinfunction "QF_5") (pintype "tri_state"))
      (node (ref "R41") (pin "11") (pinfunction "2_11") (pintype "passive"))
    )
    (net (code "70") (name "Net-(IC2-QG)") (class "Default")
      (node (ref "IC2") (pin "6") (pinfunction "QG_6") (pintype "tri_state"))
      (node (ref "R41") (pin "10") (pinfunction "2_10") (pintype "passive"))
    )
    (net (code "71") (name "Net-(IC2-QH)") (class "Default")
      (node (ref "IC2") (pin "7") (pinfunction "QH_7") (pintype "tri_state"))
      (node (ref "R41") (pin "9") (pinfunction "2_9") (pintype "passive"))
    )
    (net (code "72") (name "Net-(IC2-QH*)") (class "Default")
      (node (ref "IC2") (pin "9") (pinfunction "QH*_9") (pintype "tri_state"))
      (node (ref "IC3") (pin "14") (pinfunction "SER_14") (pintype "input"))
    )
    (net (code "73") (name "Net-(IC3-QA)") (class "Default")
      (node (ref "IC3") (pin "15") (pinfunction "QA_15") (pintype "tri_state"))
      (node (ref "R57") (pin "14") (pinfunction "2_14") (pintype "passive"))
    )
    (net (code "74") (name "Net-(IC3-QB)") (class "Default")
      (node (ref "IC3") (pin "1") (pinfunction "QB_1") (pintype "tri_state"))
      (node (ref "R57") (pin "16") (pinfunction "2_16") (pintype "passive"))
    )
    (net (code "75") (name "Net-(IC3-QC)") (class "Default")
      (node (ref "IC3") (pin "2") (pinfunction "QC_2") (pintype "tri_state"))
      (node (ref "R57") (pin "15") (pinfunction "2_15") (pintype "passive"))
    )
    (net (code "76") (name "Net-(IC3-QD)") (class "Default")
      (node (ref "IC3") (pin "3") (pinfunction "QD_3") (pintype "tri_state"))
      (node (ref "R57") (pin "13") (pinfunction "2_13") (pintype "passive"))
    )
    (net (code "77") (name "Net-(IC3-QE)") (class "Default")
      (node (ref "IC3") (pin "4") (pinfunction "QE_4") (pintype "tri_state"))
      (node (ref "R57") (pin "12") (pinfunction "2_12") (pintype "passive"))
    )
    (net (code "78") (name "Net-(IC3-QF)") (class "Default")
      (node (ref "IC3") (pin "5") (pinfunction "QF_5") (pintype "tri_state"))
      (node (ref "R57") (pin "11") (pinfunction "2_11") (pintype "passive"))
    )
    (net (code "79") (name "Net-(IC3-QG)") (class "Default")
      (node (ref "IC3") (pin "6") (pinfunction "QG_6") (pintype "tri_state"))
      (node (ref "R57") (pin "10") (pinfunction "2_10") (pintype "passive"))
    )
    (net (code "80") (name "Net-(IC3-QH)") (class "Default")
      (node (ref "IC3") (pin "7") (pinfunction "QH_7") (pintype "tri_state"))
      (node (ref "R57") (pin "9") (pinfunction "2_9") (pintype "passive"))
    )
    (net (code "81") (name "Net-(IC4-3V3OUT)") (class "Default")
      (node (ref "C23") (pin "1") (pinfunction "1_1") (pintype "passive"))
      (node (ref "IC4") (pin "10") (pinfunction "3V3OUT_10") (pintype "power_in"))
      (node (ref "IC4") (pin "11") (pinfunction "~{RESET}_11") (pintype "bidirectional"))
      (node (ref "IC4") (pin "3") (pinfunction "VCCIO_3") (pintype "power_in"))
    )
    (net (code "82") (name "Net-(IC4-USB+)") (class "Default")
      (node (ref "IC4") (pin "8") (pinfunction "USB+_8") (pintype "output"))
      (node (ref "R29") (pin "2") (pinfunction "2_2") (pintype "passive"))
      (node (ref "R30") (pin "2") (pinfunction "2_2") (pintype "passive"))
    )
    (net (code "83") (name "Net-(IC4-USB-)") (class "Default")
      (node (ref "IC4") (pin "9") (pinfunction "USB-_9") (pintype "input"))
      (node (ref "R27") (pin "2") (pinfunction "2_2") (pintype "passive"))
      (node (ref "R28") (pin "2") (pinfunction "2_2") (pintype "passive"))
    )
    (net (code "84") (name "Net-(IC4-~{RTS})") (class "Default")
      (node (ref "C43") (pin "2") (pinfunction "2_2") (pintype "passive"))
      (node (ref "IC4") (pin "2") (pinfunction "~{RTS}_2") (pintype "bidirectional"))
    )
    (net (code "85") (name "Net-(IC5-SENSE)") (class "Default")
      (node (ref "IC5") (pin "9") (pinfunction "SENSE_9") (pintype "bidirectional"))
      (node (ref "R6") (pin "2") (pinfunction "2_2") (pintype "passive"))
    )
    (net (code "86") (name "Net-(IC6-SENSE)") (class "Default")
      (node (ref "IC6") (pin "9") (pinfunction "SENSE_9") (pintype "bidirectional"))
      (node (ref "R9") (pin "2") (pinfunction "2_2") (pintype "passive"))
    )
    (net (code "87") (name "Net-(IC7-SENSE)") (class "Default")
      (node (ref "IC7") (pin "9") (pinfunction "SENSE_9") (pintype "bidirectional"))
      (node (ref "R7") (pin "2") (pinfunction "2_2") (pintype "passive"))
    )
    (net (code "88") (name "Net-(IC8-SENSE)") (class "Default")
      (node (ref "IC8") (pin "9") (pinfunction "SENSE_9") (pintype "bidirectional"))
      (node (ref "R26") (pin "2") (pinfunction "2_2") (pintype "passive"))
    )
    (net (code "89") (name "Net-(IC9-SENSE)") (class "Default")
      (node (ref "IC9") (pin "9") (pinfunction "SENSE_9") (pintype "bidirectional"))
      (node (ref "R36") (pin "2") (pinfunction "2_2") (pintype "passive"))
    )
    (net (code "90") (name "Net-(IC10-D0+)") (class "Default")
      (node (ref "C24") (pin "1") (pinfunction "1_1") (pintype "passive"))
      (node (ref "IC10") (pin "1") (pinfunction "D0+_1") (pintype "bidirectional"))
      (node (ref "R11") (pin "1") (pinfunction "1_1") (pintype "passive"))
      (node (ref "R12") (pin "1") (pinfunction "1_1") (pintype "passive"))
      (node (ref "U$1") (pin "C") (pinfunction "2_C") (pintype "passive"))
    )
    (net (code "91") (name "Net-(IC10-D0-)") (class "Default")
      (node (ref "C9") (pin "1") (pinfunction "1_1") (pintype "passive"))
      (node (ref "IC10") (pin "2") (pinfunction "D0-_2") (pintype "bidirectional"))
      (node (ref "R13") (pin "1") (pinfunction "1_1") (pintype "passive"))
      (node (ref "U$1") (pin "A") (pinfunction "1_A") (pintype "passive"))
    )
    (net (code "92") (name "Net-(IC10-D2+)") (class "Default")
      (node (ref "C30") (pin "1") (pinfunction "1_1") (pintype "passive"))
      (node (ref "IC10") (pin "16") (pinfunction "D2+_16") (pintype "bidirectional"))
      (node (ref "R16") (pin "2") (pinfunction "2_2") (pintype "passive"))
    )
    (net (code "93") (name "Net-(IC10-D2-)") (class "Default")
      (node (ref "C29") (pin "1") (pinfunction "1_1") (pintype "passive"))
      (node (ref "IC10") (pin "15") (pinfunction "D2-_15") (pintype "bidirectional"))
      (node (ref "R17") (pin "2") (pinfunction "2_2") (pintype "passive"))
    )
    (net (code "94") (name "Net-(IC10-D3+)") (class "Default")
      (node (ref "C28") (pin "1") (pinfunction "1_1") (pintype "passive"))
      (node (ref "IC10") (pin "20") (pinfunction "D3+_20") (pintype "bidirectional"))
      (node (ref "R18") (pin "2") (pinfunction "2_2") (pintype "passive"))
    )
    (net (code "95") (name "Net-(IC10-D3-)") (class "Default")
      (node (ref "C27") (pin "1") (pinfunction "1_1") (pintype "passive"))
      (node (ref "IC10") (pin "19") (pinfunction "D3-_19") (pintype "bidirectional"))
      (node (ref "R19") (pin "2") (pinfunction "2_2") (pintype "passive"))
    )
    (net (code "96") (name "Net-(IC10-D4+)") (class "Default")
      (node (ref "C26") (pin "1") (pinfunction "1_1") (pintype "passive"))
      (node (ref "IC10") (pin "24") (pinfunction "D4+_24") (pintype "bidirectional"))
      (node (ref "R21") (pin "2") (pinfunction "2_2") (pintype "passive"))
    )
    (net (code "97") (name "Net-(IC10-D4-)") (class "Default")
      (node (ref "C25") (pin "1") (pinfunction "1_1") (pintype "passive"))
      (node (ref "IC10") (pin "23") (pinfunction "D4-_23") (pintype "bidirectional"))
      (node (ref "R20") (pin "2") (pinfunction "2_2") (pintype "passive"))
    )
    (net (code "98") (name "Net-(IC10-XTAL1)") (class "Default")
      (node (ref "IC10") (pin "30") (pinfunction "XTAL1_30") (pintype "bidirectional"))
      (node (ref "Y2") (pin "3") (pinfunction "3_3") (pintype "passive"))
    )
    (net (code "99") (name "Net-(IC10-XTAL2)") (class "Default")
      (node (ref "IC10") (pin "29") (pinfunction "XTAL2_29") (pintype "bidirectional"))
      (node (ref "Y2") (pin "1") (pinfunction "1_1") (pintype "passive"))
    )
    (net (code "100") (name "Net-(ISP2-RST)") (class "Default")
      (node (ref "ISP2") (pin "5") (pinfunction "RST_5") (pintype "output"))
      (node (ref "R32") (pin "1") (pinfunction "1_1") (pintype "passive"))
    )
    (net (code "101") (name "Net-(ISP3-RST)") (class "Default")
      (node (ref "ISP3") (pin "5") (pinfunction "RST_5") (pintype "output"))
      (node (ref "R33") (pin "1") (pinfunction "1_1") (pintype "passive"))
    )
    (net (code "102") (name "Net-(ISP4-RST)") (class "Default")
      (node (ref "ISP4") (pin "5") (pinfunction "RST_5") (pintype "output"))
      (node (ref "R38") (pin "1") (pinfunction "1_1") (pintype "passive"))
    )
    (net (code "103") (name "Net-(ISP5-RST)") (class "Default")
      (node (ref "ISP5") (pin "5") (pinfunction "RST_5") (pintype "output"))
      (node (ref "R39") (pin "1") (pinfunction "1_1") (pintype "passive"))
    )
    (net (code "104") (name "Net-(JP8-Pad1)") (class "Default")
      (node (ref "JP8") (pin "1") (pinfunction "1_1") (pintype "passive"))
      (node (ref "R12") (pin "2") (pinfunction "2_2") (pintype "passive"))
    )
    (net (code "105") (name "Net-(JP8-Pad2)") (class "Default")
      (node (ref "JP8") (pin "2") (pinfunction "2_2") (pintype "passive"))
      (node (ref "R13") (pin "2") (pinfunction "2_2") (pintype "passive"))
    )
    (net (code "106") (name "Net-(L2-2)") (class "Default")
      (node (ref "F3") (pin "1") (pinfunction "1_1") (pintype "passive"))
      (node (ref "L2") (pin "P$2") (pinfunction "2_P$2") (pintype "passive"))
    )
    (net (code "107") (name "Net-(L3-2)") (class "Default")
      (node (ref "F2") (pin "1") (pinfunction "1_1") (pintype "passive"))
      (node (ref "L3") (pin "P$2") (pinfunction "2_P$2") (pintype "passive"))
    )
    (net (code "108") (name "Net-(L4-2)") (class "Default")
      (node (ref "F1") (pin "1") (pinfunction "1_1") (pintype "passive"))
      (node (ref "L4") (pin "P$2") (pinfunction "2_P$2") (pintype "passive"))
    )
    (net (code "109") (name "Net-(LED3-PadC)") (class "Default")
      (node (ref "LED3") (pin "C") (pinfunction "C_C") (pintype "passive"))
      (node (ref "R34") (pin "1") (pinfunction "1_1") (pintype "passive"))
    )
    (net (code "110") (name "Net-(Q1-D)") (class "Default")
      (node (ref "JP14") (pin "1") (pinfunction "1_1") (pintype "passive"))
      (node (ref "Q1") (pin "3") (pinfunction "D_3") (pintype "bidirectional"))
    )
    (net (code "111") (name "Net-(Q2-D)") (class "Default")
      (node (ref "JP15") (pin "1") (pinfunction "1_1") (pintype "passive"))
      (node (ref "Q2") (pin "3") (pinfunction "D_3") (pintype "bidirectional"))
    )
    (net (code "112") (name "Net-(Q3-D)") (class "Default")
      (node (ref "JP16") (pin "1") (pinfunction "1_1") (pintype "passive"))
      (node (ref "Q3") (pin "3") (pinfunction "D_3") (pintype "bidirectional"))
    )
    (net (code "113") (name "Net-(U$2-1)") (class "Default")
      (node (ref "JP17") (pin "2") (pinfunction "2_2") (pintype "passive"))
      (node (ref "R15") (pin "1") (pinfunction "1_1") (pintype "passive"))
      (node (ref "R21") (pin "1") (pinfunction "1_1") (pintype "passive"))
      (node (ref "U$2") (pin "A") (pinfunction "1_A") (pintype "passive"))
    )
    (net (code "114") (name "Net-(U$2-2)") (class "Default")
      (node (ref "JP17") (pin "3") (pinfunction "3_3") (pintype "passive"))
      (node (ref "R14") (pin "1") (pinfunction "1_1") (pintype "passive"))
      (node (ref "R20") (pin "1") (pinfunction "1_1") (pintype "passive"))
      (node (ref "U$2") (pin "C") (pinfunction "2_C") (pintype "passive"))
    )
    (net (code "115") (name "Net-(U$3-1)") (class "Default")
      (node (ref "JP13") (pin "2") (pinfunction "2_2") (pintype "passive"))
      (node (ref "R18") (pin "1") (pinfunction "1_1") (pintype "passive"))
      (node (ref "R23") (pin "1") (pinfunction "1_1") (pintype "passive"))
      (node (ref "U$3") (pin "A") (pinfunction "1_A") (pintype "passive"))
    )
    (net (code "116") (name "Net-(U$3-2)") (class "Default")
      (node (ref "JP13") (pin "3") (pinfunction "3_3") (pintype "passive"))
      (node (ref "R19") (pin "1") (pinfunction "1_1") (pintype "passive"))
      (node (ref "R22") (pin "1") (pinfunction "1_1") (pintype "passive"))
      (node (ref "U$3") (pin "C") (pinfunction "2_C") (pintype "passive"))
    )
    (net (code "117") (name "Net-(U$4-1)") (class "Default")
      (node (ref "JP11") (pin "2") (pinfunction "2_2") (pintype "passive"))
      (node (ref "R16") (pin "1") (pinfunction "1_1") (pintype "passive"))
      (node (ref "R25") (pin "1") (pinfunction "1_1") (pintype "passive"))
      (node (ref "U$4") (pin "A") (pinfunction "1_A") (pintype "passive"))
    )
    (net (code "118") (name "Net-(U$4-2)") (class "Default")
      (node (ref "JP11") (pin "3") (pinfunction "3_3") (pintype "passive"))
      (node (ref "R17") (pin "1") (pinfunction "1_1") (pintype "passive"))
      (node (ref "R24") (pin "1") (pinfunction "1_1") (pintype "passive"))
      (node (ref "U$4") (pin "C") (pinfunction "2_C") (pintype "passive"))
    )
    (net (code "119") (name "Net-(U$6-2)") (class "Default")
      (node (ref "C53") (pin "+") (pinfunction "+_+") (pintype "passive"))
      (node (ref "F7") (pin "1") (pinfunction "1_1") (pintype "bidirectional"))
      (node (ref "JP14") (pin "2") (pinfunction "2_2") (pintype "passive"))
      (node (ref "SJ1") (pin "1") (pinfunction "1_1") (pintype "passive"))
      (node (ref "U$6") (pin "C") (pinfunction "2_C") (pintype "passive"))
    )
    (net (code "120") (name "Net-(U$7-2)") (class "Default")
      (node (ref "C54") (pin "+") (pinfunction "+_+") (pintype "passive"))
      (node (ref "F5") (pin "1") (pinfunction "1_1") (pintype "bidirectional"))
      (node (ref "JP15") (pin "2") (pinfunction "2_2") (pintype "passive"))
      (node (ref "SJ2") (pin "1") (pinfunction "1_1") (pintype "passive"))
      (node (ref "U$7") (pin "C") (pinfunction "2_C") (pintype "passive"))
    )
    (net (code "121") (name "Net-(U$8-2)") (class "Default")
      (node (ref "C55") (pin "+") (pinfunction "+_+") (pintype "passive"))
      (node (ref "F6") (pin "1") (pinfunction "1_1") (pintype "bidirectional"))
      (node (ref "JP16") (pin "2") (pinfunction "2_2") (pintype "passive"))
      (node (ref "SJ3") (pin "1") (pinfunction "1_1") (pintype "passive"))
      (node (ref "U$8") (pin "C") (pinfunction "2_C") (pintype "passive"))
    )
    (net (code "122") (name "Net-(U3-PB6(XTAL1{slash}TOSC1))") (class "Default")
      (node (ref "U3") (pin "7") (pinfunction "PB6(XTAL1/TOSC1)_7") (pintype "bidirectional"))
      (node (ref "Y1") (pin "1") (pinfunction "1_1") (pintype "passive"))
    )
    (net (code "123") (name "Net-(U3-PB7(XTAL2{slash}TOSC2))") (class "Default")
      (node (ref "U3") (pin "8") (pinfunction "PB7(XTAL2/TOSC2)_8") (pintype "bidirectional"))
      (node (ref "Y1") (pin "3") (pinfunction "3_3") (pintype "passive"))
    )
    (net (code "124") (name "unconnected-(IC3-QH*-Pad9)") (class "Default")
      (node (ref "IC3") (pin "9") (pinfunction "QH*_9") (pintype "tri_state"))
    )
    (net (code "125") (name "unconnected-(IC4-CBUS0-Pad15)") (class "Default")
      (node (ref "IC4") (pin "15") (pinfunction "CBUS0_15") (pintype "bidirectional"))
    )
    (net (code "126") (name "unconnected-(IC4-CBUS1-Pad14)") (class "Default")
      (node (ref "IC4") (pin "14") (pinfunction "CBUS1_14") (pintype "bidirectional"))
    )
    (net (code "127") (name "unconnected-(IC4-CBUS2-Pad7)") (class "Default")
      (node (ref "IC4") (pin "7") (pinfunction "CBUS2_7") (pintype "bidirectional"))
    )
    (net (code "128") (name "unconnected-(IC4-CBUS3-Pad16)") (class "Default")
      (node (ref "IC4") (pin "16") (pinfunction "CBUS3_16") (pintype "bidirectional"))
    )
    (net (code "129") (name "unconnected-(IC4-~{CTS}-Pad6)") (class "Default")
      (node (ref "IC4") (pin "6") (pinfunction "~{CTS}_6") (pintype "bidirectional"))
    )
    (net (code "130") (name "unconnected-(IC5-STAT4-Pad11)") (class "Default")
      (node (ref "IC5") (pin "11") (pinfunction "STAT4_11") (pintype "bidirectional"))
    )
    (net (code "131") (name "unconnected-(IC6-STAT4-Pad11)") (class "Default")
      (node (ref "IC6") (pin "11") (pinfunction "STAT4_11") (pintype "bidirectional"))
    )
    (net (code "132") (name "unconnected-(IC7-STAT4-Pad11)") (class "Default")
      (node (ref "IC7") (pin "11") (pinfunction "STAT4_11") (pintype "bidirectional"))
    )
    (net (code "133") (name "unconnected-(IC8-STAT4-Pad11)") (class "Default")
      (node (ref "IC8") (pin "11") (pinfunction "STAT4_11") (pintype "bidirectional"))
    )
    (net (code "134") (name "unconnected-(IC9-STAT4-Pad11)") (class "Default")
      (node (ref "IC9") (pin "11") (pinfunction "STAT4_11") (pintype "bidirectional"))
    )
    (net (code "135") (name "unconnected-(IC10-EECLK-Pad5)") (class "Default")
      (node (ref "IC10") (pin "5") (pinfunction "EECLK_5") (pintype "bidirectional"))
    )
    (net (code "136") (name "unconnected-(IC10-SUSPND-Pad32)") (class "Default")
      (node (ref "IC10") (pin "32") (pinfunction "SUSPND_32") (pintype "bidirectional"))
    )
    (net (code "137") (name "unconnected-(IC10-~{PWRON1}-Pad9)") (class "Default")
      (node (ref "IC10") (pin "9") (pinfunction "~{PWRON1}_9") (pintype "bidirectional"))
    )
    (net (code "138") (name "unconnected-(IC10-~{PWRON2}-Pad13)") (class "Default")
      (node (ref "IC10") (pin "13") (pinfunction "~{PWRON2}_13") (pintype "bidirectional"))
    )
    (net (code "139") (name "unconnected-(IC10-~{PWRON3}-Pad17)") (class "Default")
      (node (ref "IC10") (pin "17") (pinfunction "~{PWRON3}_17") (pintype "bidirectional"))
    )
    (net (code "140") (name "unconnected-(IC10-~{PWRON4}-Pad21)") (class "Default")
      (node (ref "IC10") (pin "21") (pinfunction "~{PWRON4}_21") (pintype "bidirectional"))
    )
    (net (code "141") (name "unconnected-(U2-BP-Pad4)") (class "Default")
      (node (ref "U2") (pin "4") (pinfunction "BP_4") (pintype "input"))
    )
  )
)
